# 612_jetracer_esp32s3_030004.net
KiCad netlist of a schematic drawn in EAGLE
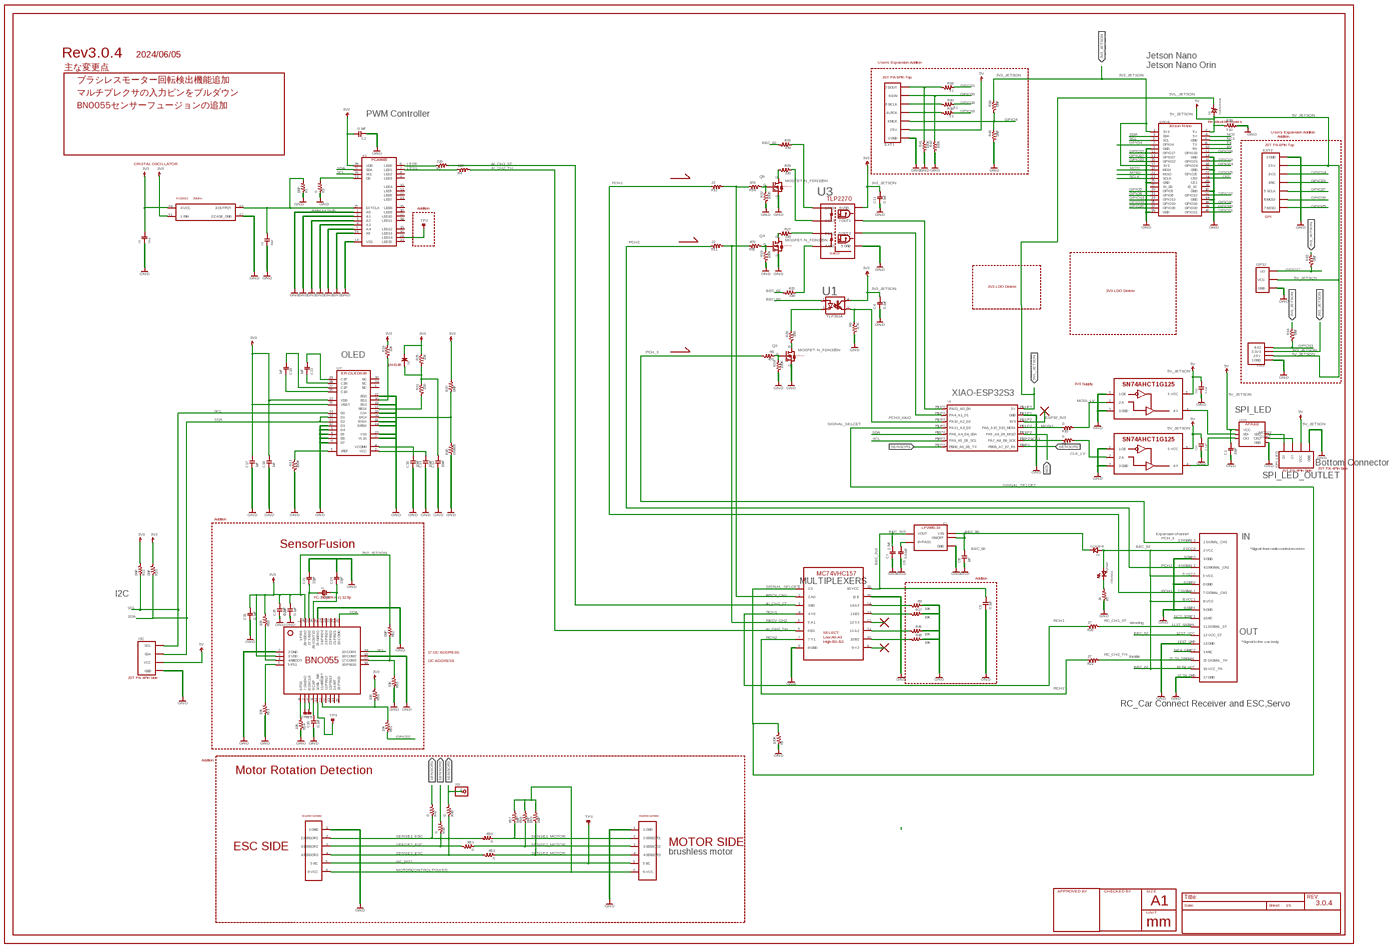
[diagram p0: schematic, sheet 1, overview]
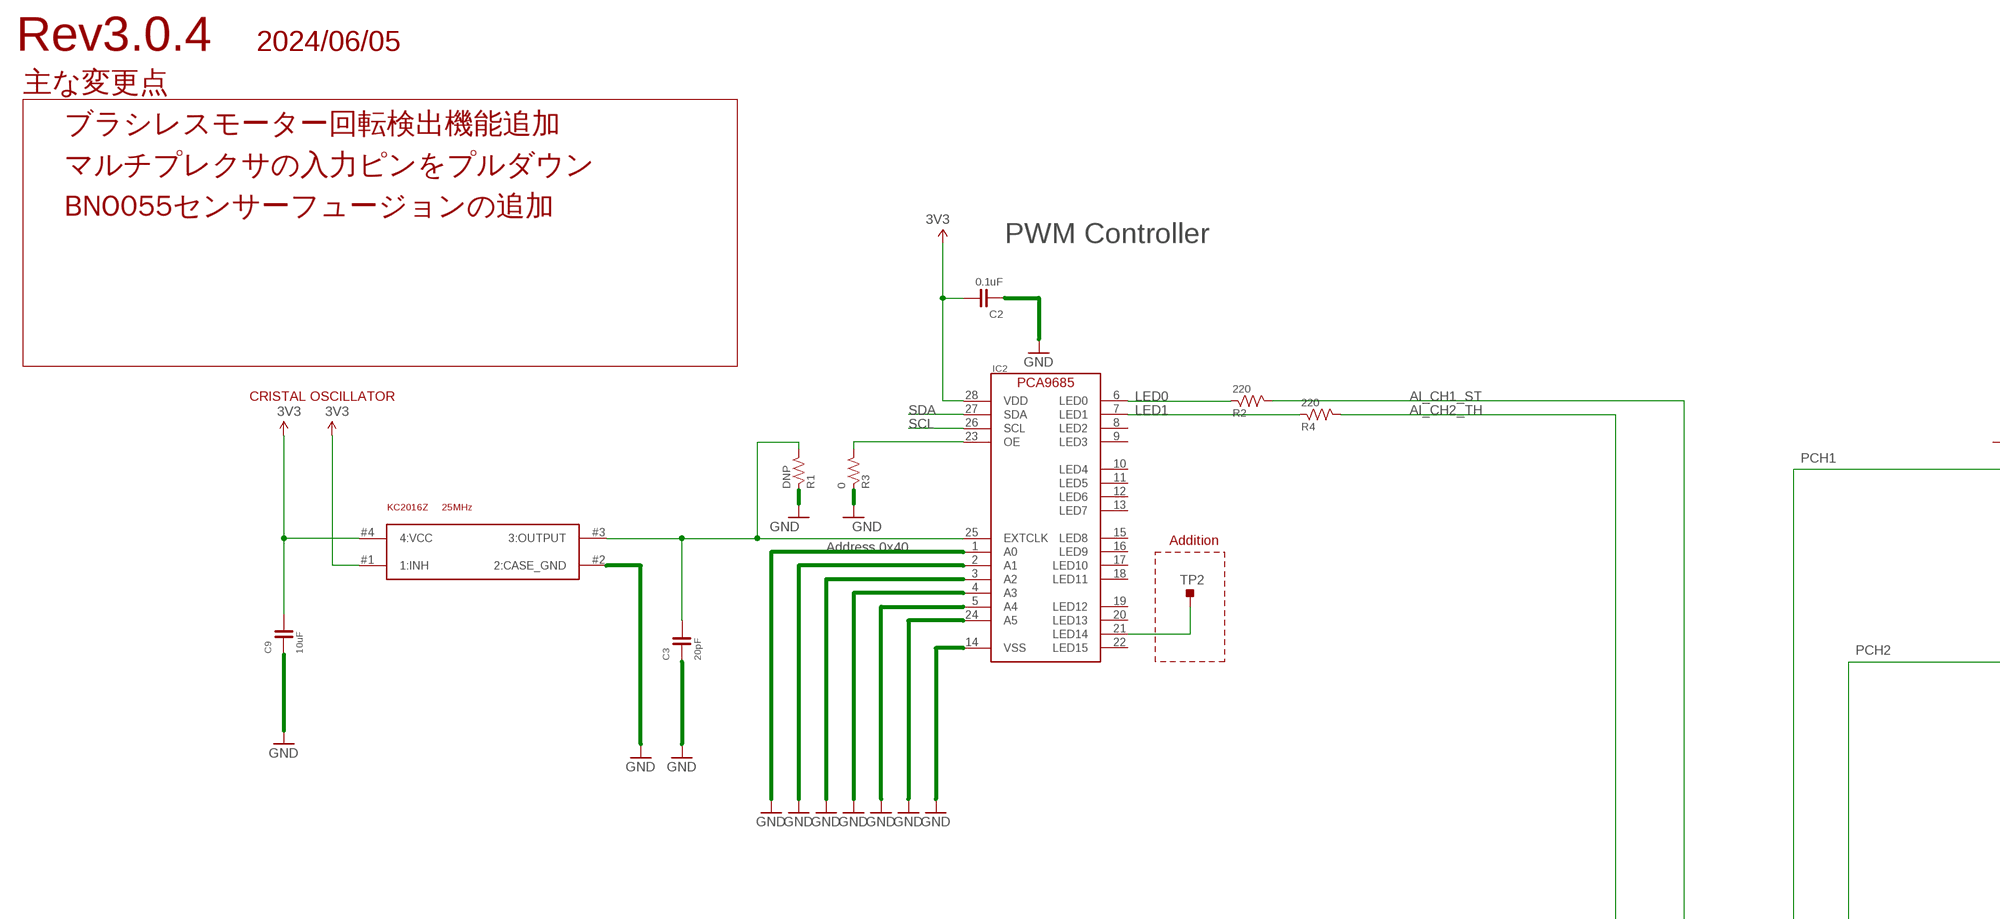
[diagram p1: schematic, sheet 1, part 1 of 4]
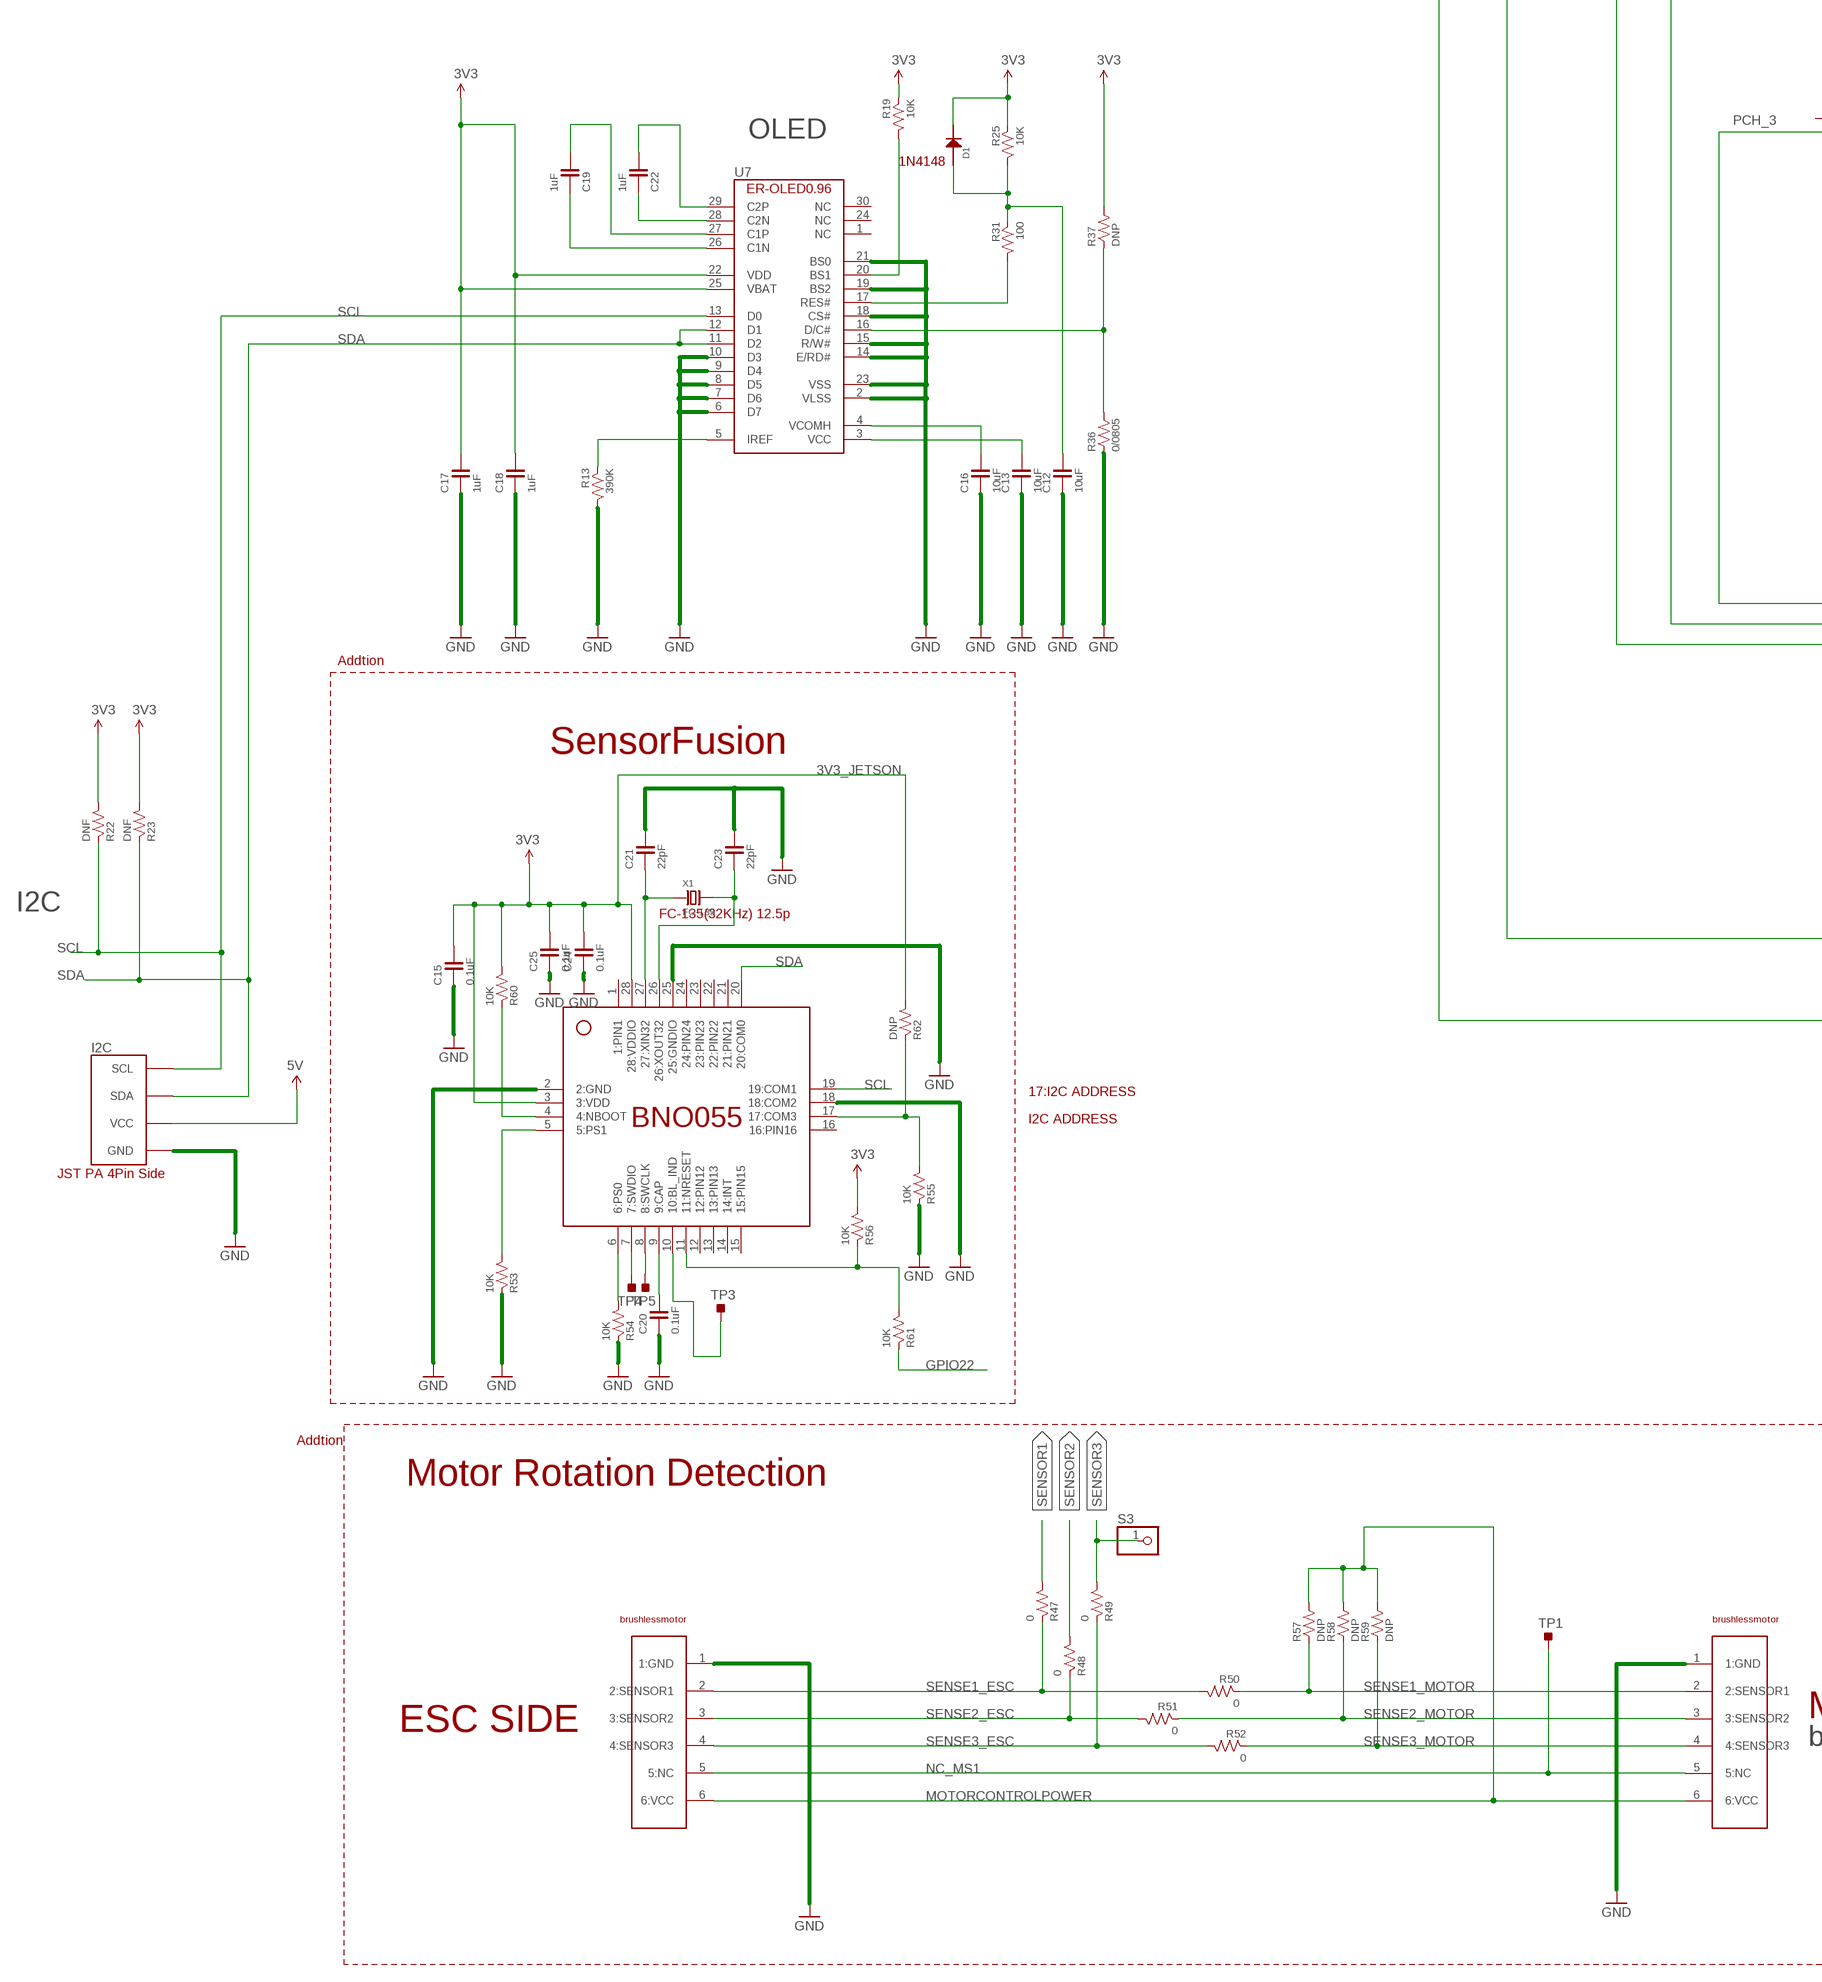
[diagram p2: schematic, sheet 1, part 2 of 4]
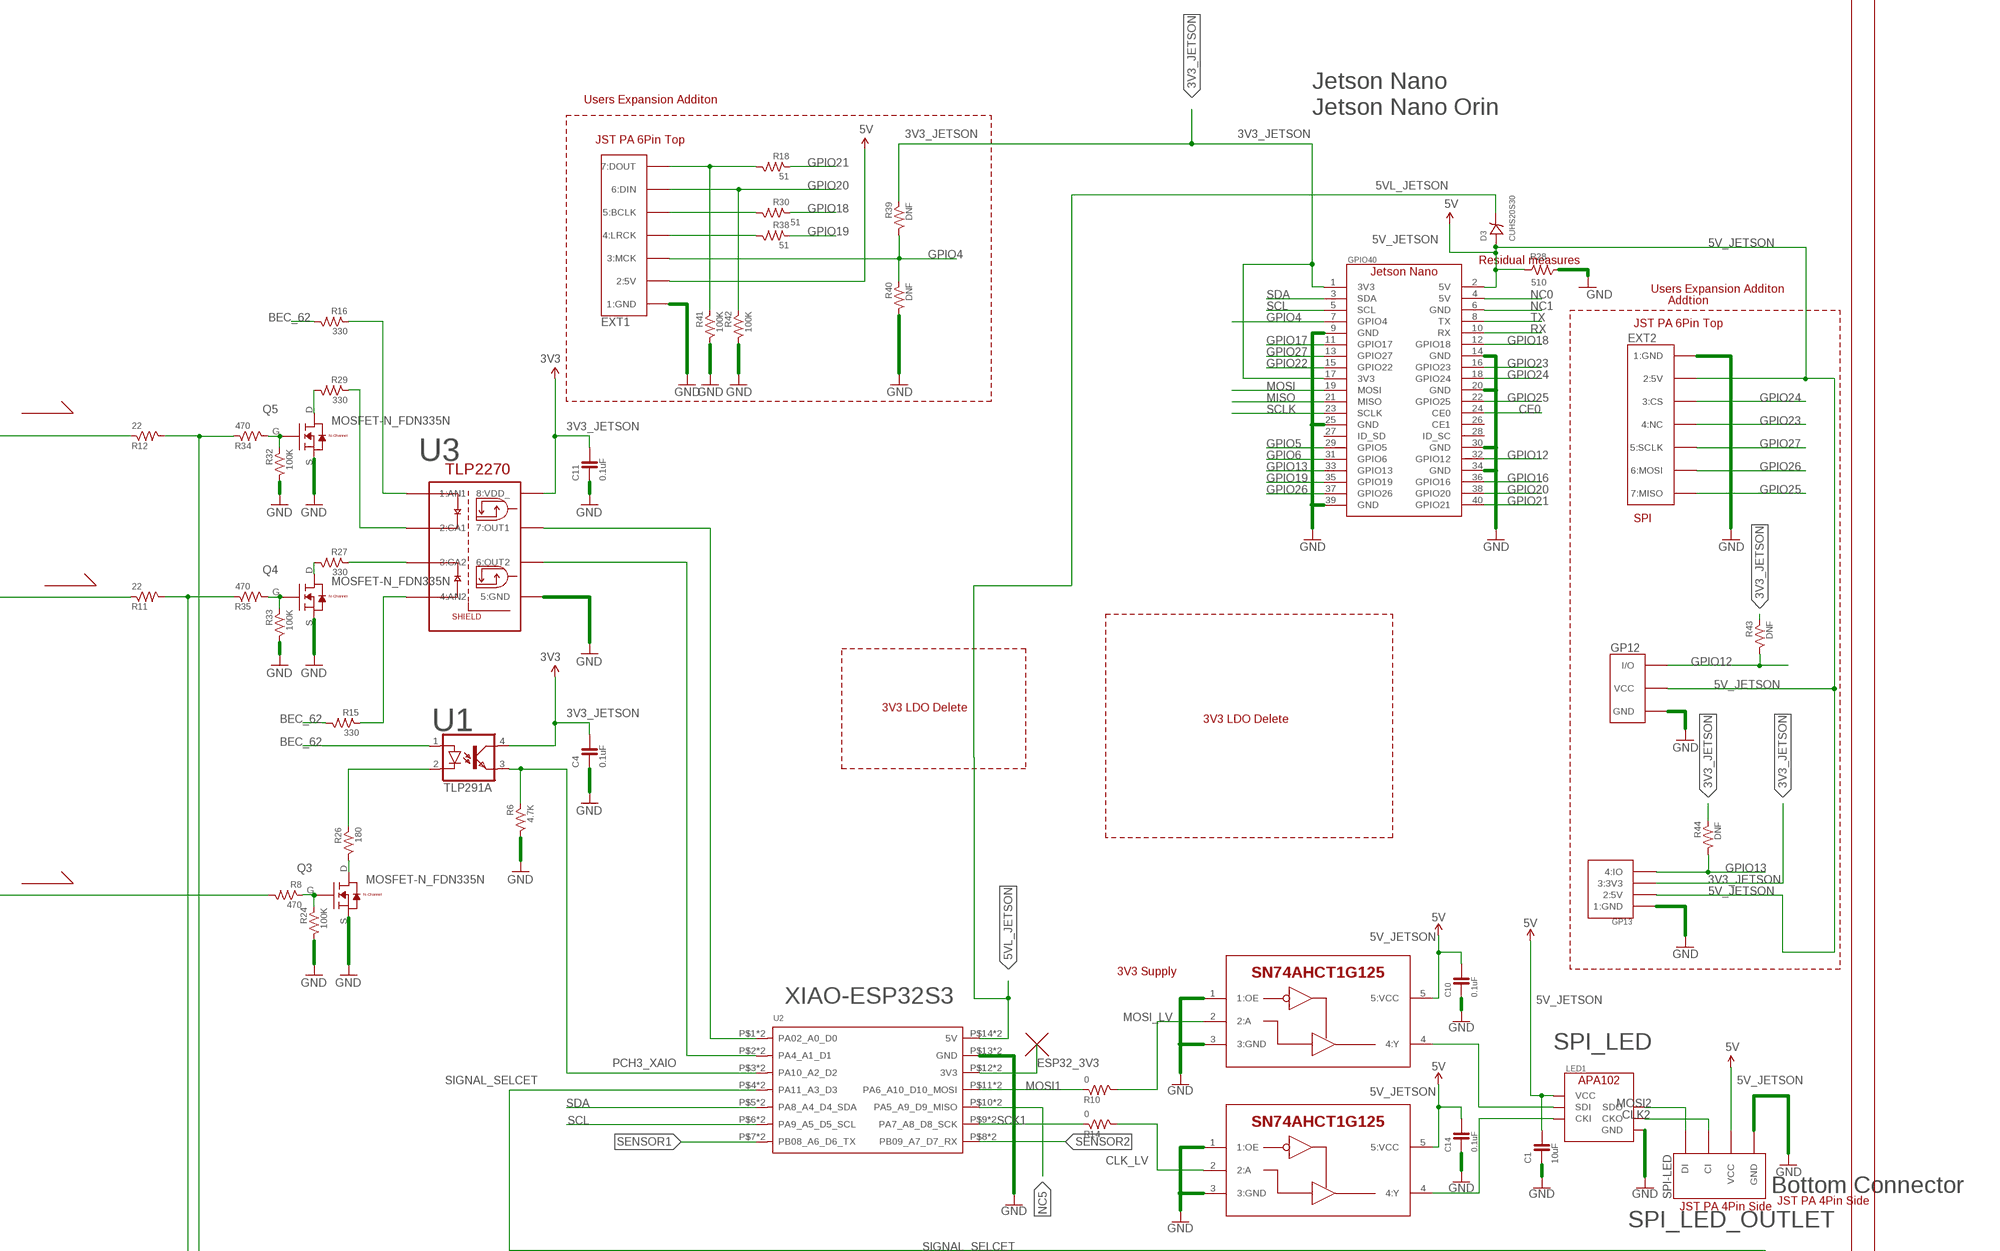
[diagram p3: schematic, sheet 1, part 3 of 4]
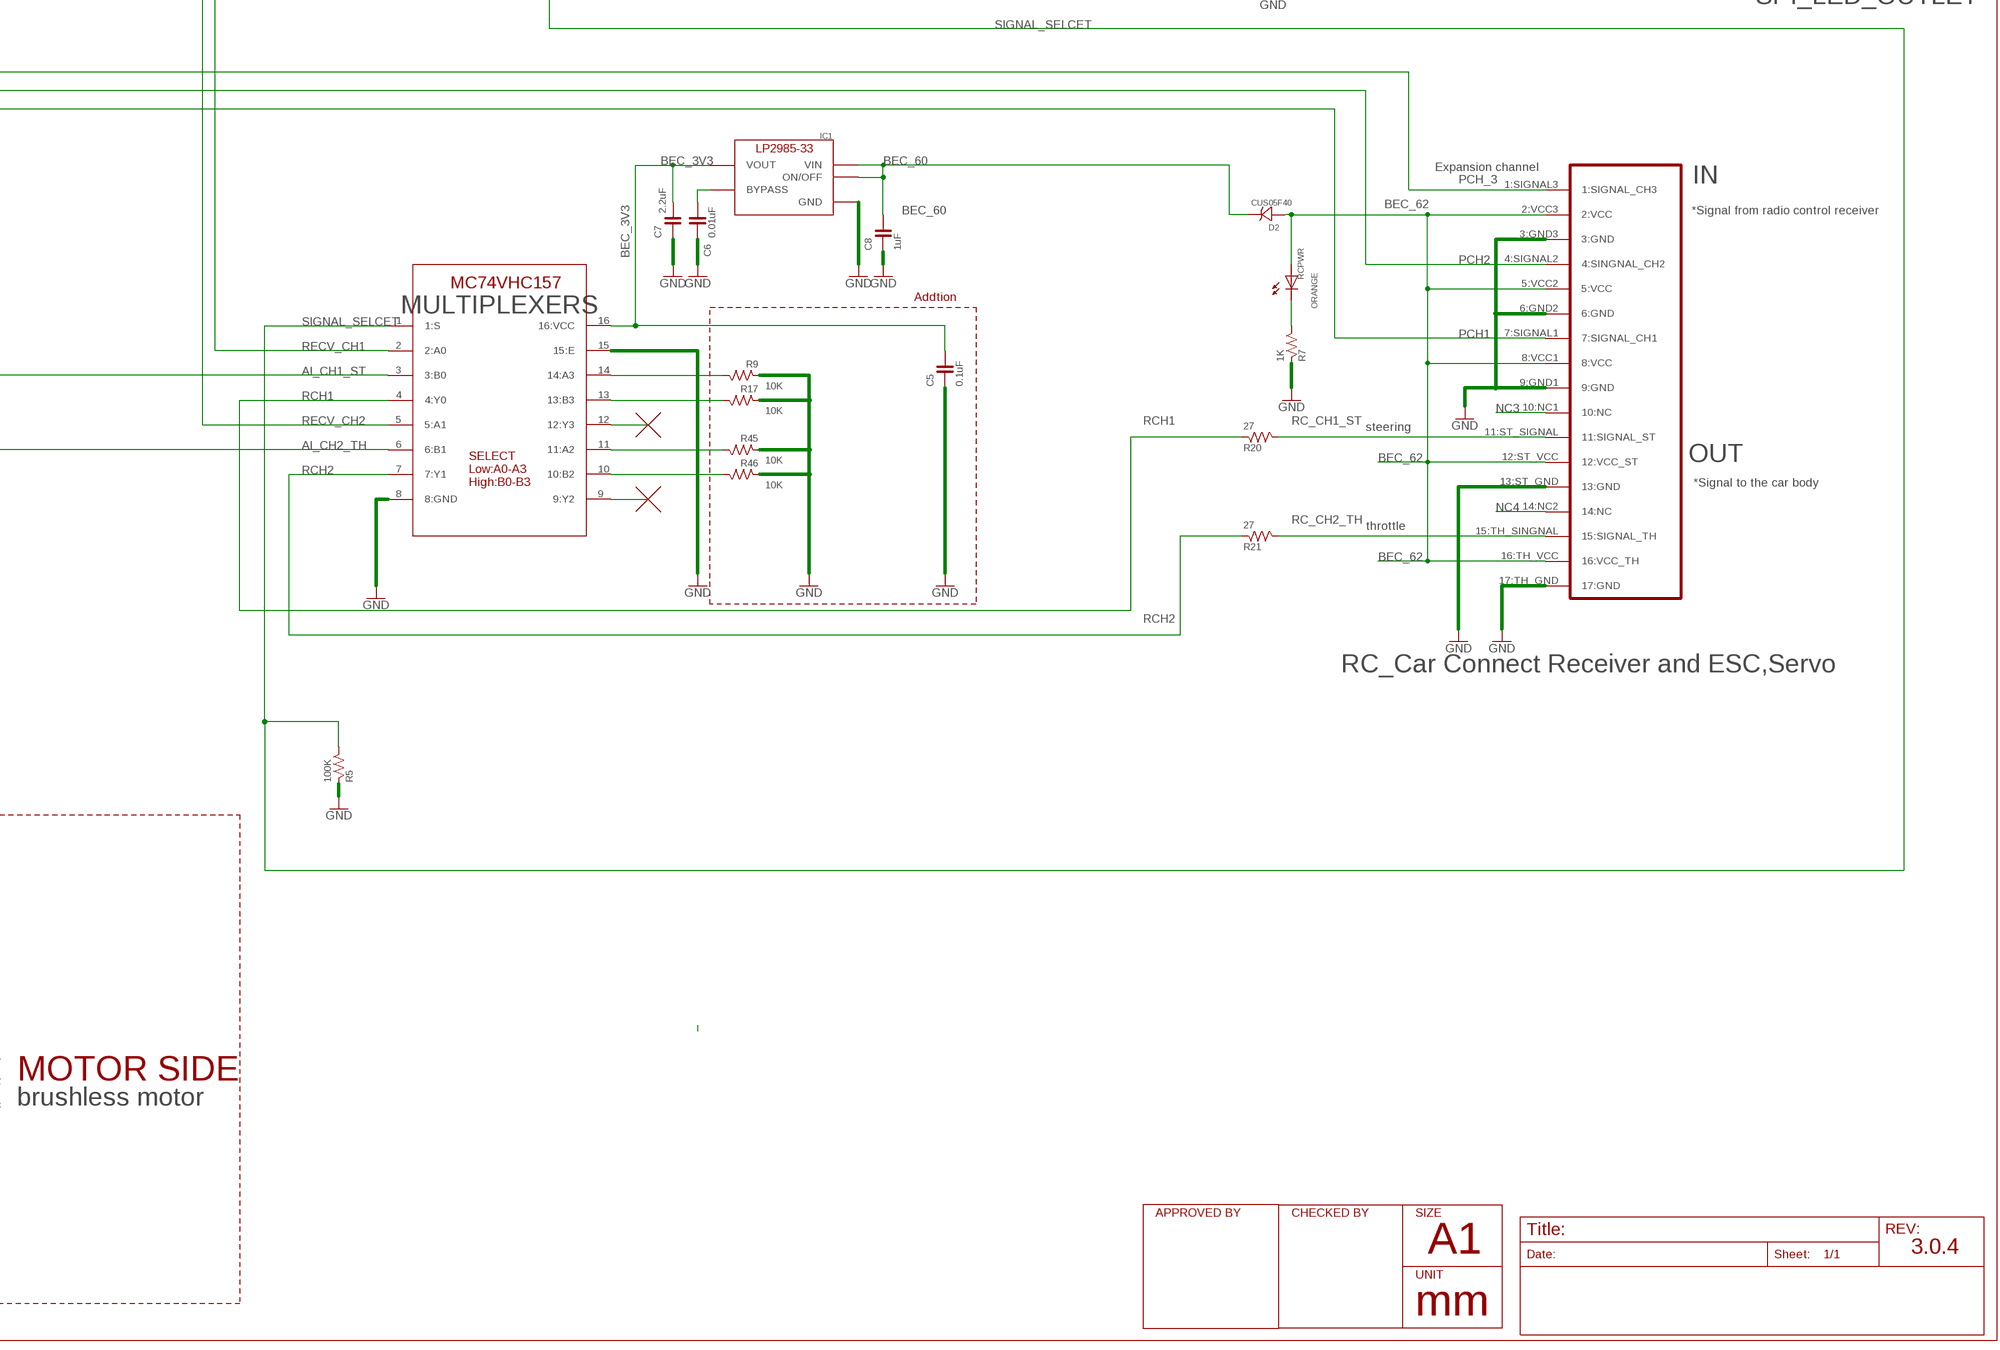
[diagram p4: schematic, sheet 1, part 4 of 4]

(export (version "E")
  (design (tool "Eeschema 10.0.6"))
  (components
    (comp (ref "C1")
      (value "10uF")
      (footprint "eagle-import:0603")
      (libsource (lib "eagle-import") (part "CAPACITOR-0603"))
    )
    (comp (ref "C2")
      (value "0.1uF")
      (footprint "eagle-import:0603")
      (libsource (lib "eagle-import") (part "CAPACITOR-0603"))
    )
    (comp (ref "C3")
      (value "20pF")
      (footprint "eagle-import:0402")
      (libsource (lib "eagle-import") (part "CAPACITOR-0402"))
    )
    (comp (ref "C4")
      (value "0.1uF")
      (footprint "eagle-import:0603")
      (libsource (lib "eagle-import") (part "CAPACITOR-0603"))
    )
    (comp (ref "C5")
      (value "0.1uF")
      (footprint "eagle-import:0603")
      (libsource (lib "eagle-import") (part "CAPACITOR-0603"))
    )
    (comp (ref "C6")
      (value "0.01uF")
      (footprint "eagle-import:0603")
      (libsource (lib "eagle-import") (part "CAPACITOR-0603"))
    )
    (comp (ref "C7")
      (value "2.2uF")
      (footprint "eagle-import:0603")
      (libsource (lib "eagle-import") (part "CAPACITOR-0603"))
    )
    (comp (ref "C8")
      (value "1uF")
      (footprint "eagle-import:0603")
      (libsource (lib "eagle-import") (part "CAPACITOR-0603"))
    )
    (comp (ref "C9")
      (value "10uF")
      (footprint "eagle-import:0402")
      (libsource (lib "eagle-import") (part "CAPACITOR-0402"))
    )
    (comp (ref "C10")
      (value "0.1uF")
      (footprint "eagle-import:0402")
      (libsource (lib "eagle-import") (part "CAPACITOR-0402"))
    )
    (comp (ref "C11")
      (value "0.1uF")
      (footprint "eagle-import:0603")
      (libsource (lib "eagle-import") (part "CAPACITOR-0603"))
    )
    (comp (ref "C12")
      (value "10uF")
      (footprint "eagle-import:0603")
      (libsource (lib "eagle-import") (part "CAPACITOR-0603"))
    )
    (comp (ref "C13")
      (value "10uF")
      (footprint "eagle-import:0603")
      (libsource (lib "eagle-import") (part "CAPACITOR-0603"))
    )
    (comp (ref "C14")
      (value "0.1uF")
      (footprint "eagle-import:0402")
      (libsource (lib "eagle-import") (part "CAPACITOR-0402"))
    )
    (comp (ref "C15")
      (value "0.1uF")
      (footprint "eagle-import:0402")
      (libsource (lib "eagle-import") (part "CAPACITOR-0402"))
    )
    (comp (ref "C16")
      (value "10uF")
      (footprint "eagle-import:0603")
      (libsource (lib "eagle-import") (part "CAPACITOR-0603"))
    )
    (comp (ref "C17")
      (value "1uF")
      (footprint "eagle-import:0603")
      (libsource (lib "eagle-import") (part "CAPACITOR-0603"))
    )
    (comp (ref "C18")
      (value "1uF")
      (footprint "eagle-import:0603")
      (libsource (lib "eagle-import") (part "CAPACITOR-0603"))
    )
    (comp (ref "C19")
      (value "1uF")
      (footprint "eagle-import:0603")
      (libsource (lib "eagle-import") (part "CAPACITOR-0603"))
    )
    (comp (ref "C20")
      (value "0.1uF")
      (footprint "eagle-import:0402")
      (libsource (lib "eagle-import") (part "CAPACITOR-0402"))
    )
    (comp (ref "C21")
      (value "22pF")
      (footprint "eagle-import:0402")
      (libsource (lib "eagle-import") (part "CAPACITOR-0402"))
    )
    (comp (ref "C22")
      (value "1uF")
      (footprint "eagle-import:0603")
      (libsource (lib "eagle-import") (part "CAPACITOR-0603"))
    )
    (comp (ref "C23")
      (value "22pF")
      (footprint "eagle-import:0402")
      (libsource (lib "eagle-import") (part "CAPACITOR-0402"))
    )
    (comp (ref "C24")
      (value "0.1uF")
      (footprint "eagle-import:0402")
      (libsource (lib "eagle-import") (part "CAPACITOR-0402"))
    )
    (comp (ref "C25")
      (value "0.1uF")
      (footprint "eagle-import:0402")
      (libsource (lib "eagle-import") (part "CAPACITOR-0402"))
    )
    (comp (ref "D1")
      (value "1N4148")
      (footprint "eagle-import:1N4148W")
      (libsource (lib "eagle-import") (part "1N4148"))
    )
    (comp (ref "D2")
      (value "CUS05F40")
      (footprint "eagle-import:CUS05F40")
      (libsource (lib "eagle-import") (part "CUS05F40"))
    )
    (comp (ref "D3")
      (value "CUHS20S30")
      (footprint "eagle-import:US2H")
      (libsource (lib "eagle-import") (part "CUHS20S30"))
    )
    (comp (ref "ESC_CON")
      (value "BRUSHLESSMOTOR_CON")
      (footprint "eagle-import:B6B-ZR")
      (libsource (lib "eagle-import") (part "BRUSHLESSMOTOR_CON"))
    )
    (comp (ref "EXT1")
      (value "FABO-I2S-7PIN")
      (footprint "eagle-import:SPI-B07B-PASK-1")
      (libsource (lib "eagle-import") (part "FABO-I2S-7PIN"))
    )
    (comp (ref "EXT2")
      (value "FABO-SPI-7PIN")
      (footprint "eagle-import:SPI-B07B-PASK-1")
      (libsource (lib "eagle-import") (part "FABO-SPI-7PIN"))
    )
    (comp (ref "GP12")
      (value "FABO_BRICK_3PIN-B03B-PASK-1")
      (footprint "eagle-import:FABO_BRICK_3PIN_B03B-PASK-1")
      (libsource (lib "eagle-import") (part "FABO_BRICK_3PIN-B03B-PASK-1"))
    )
    (comp (ref "GP13")
      (value "FABO-GPIO-2G")
      (footprint "eagle-import:GPIO-B04B-PASK-1")
      (libsource (lib "eagle-import") (part "FABO-GPIO-2G"))
    )
    (comp (ref "GPIO40")
      (value "JETSON_NANOJETSON_NANO_OVERALL")
      (footprint "eagle-import:JETSON_NANO_DEMENTION")
      (libsource (lib "eagle-import") (part "JETSON_NANOJETSON_NANO_OVERALL"))
    )
    (comp (ref "I2C")
      (value "FABO-I2C")
      (footprint "eagle-import:I2C-SM04B-PASS-1-FL")
      (libsource (lib "eagle-import") (part "FABO-I2C"))
    )
    (comp (ref "IC1")
      (value "LP2985-33DBVR")
      (footprint "eagle-import:SOT-23-5")
      (libsource (lib "eagle-import") (part "LP2985-33DBVR"))
    )
    (comp (ref "IC2")
      (value "PCA9685PW,BS")
      (footprint "eagle-import:PCA9685")
      (libsource (lib "eagle-import") (part "PCA9685PW,BS"))
    )
    (comp (ref "LED1")
      (value "APA102_IPIXEL")
      (footprint "eagle-import:APA102_2020")
      (libsource (lib "eagle-import") (part "APA102_IPIXEL"))
    )
    (comp (ref "MOTOR")
      (value "BRUSHLESSMOTOR_CON")
      (footprint "eagle-import:B6B-ZR")
      (libsource (lib "eagle-import") (part "BRUSHLESSMOTOR_CON"))
    )
    (comp (ref "Q3")
      (value "MOSFET-N_FDN335N")
      (footprint "eagle-import:SUPERSOT-3")
      (libsource (lib "eagle-import") (part "MOSFET-N_FDN335N"))
    )
    (comp (ref "Q4")
      (value "MOSFET-N_FDN335N")
      (footprint "eagle-import:SUPERSOT-3")
      (libsource (lib "eagle-import") (part "MOSFET-N_FDN335N"))
    )
    (comp (ref "Q5")
      (value "MOSFET-N_FDN335N")
      (footprint "eagle-import:SUPERSOT-3")
      (libsource (lib "eagle-import") (part "MOSFET-N_FDN335N"))
    )
    (comp (ref "R1")
      (value "DNP")
      (footprint "eagle-import:0603")
      (libsource (lib "eagle-import") (part "RESISTOR-0603"))
    )
    (comp (ref "R2")
      (value "220")
      (footprint "eagle-import:0603")
      (libsource (lib "eagle-import") (part "RESISTOR-0603"))
    )
    (comp (ref "R3")
      (value "0")
      (footprint "eagle-import:0603")
      (libsource (lib "eagle-import") (part "RESISTOR-0603"))
    )
    (comp (ref "R4")
      (value "220")
      (footprint "eagle-import:0603")
      (libsource (lib "eagle-import") (part "RESISTOR-0603"))
    )
    (comp (ref "R5")
      (value "100K")
      (footprint "eagle-import:0603")
      (libsource (lib "eagle-import") (part "RESISTOR-0603"))
    )
    (comp (ref "R6")
      (value "4.7K")
      (footprint "eagle-import:0603")
      (libsource (lib "eagle-import") (part "RESISTOR-0603"))
    )
    (comp (ref "R7")
      (value "1K")
      (footprint "eagle-import:0603")
      (libsource (lib "eagle-import") (part "RESISTOR-0603"))
    )
    (comp (ref "R8")
      (value "470")
      (footprint "eagle-import:0603")
      (libsource (lib "eagle-import") (part "RESISTOR-0603"))
    )
    (comp (ref "R9")
      (value "10K")
      (footprint "eagle-import:0603")
      (libsource (lib "eagle-import") (part "RESISTOR-0603"))
    )
    (comp (ref "R10")
      (value "0")
      (footprint "eagle-import:0603")
      (libsource (lib "eagle-import") (part "RESISTOR-0603"))
    )
    (comp (ref "R11")
      (value "22")
      (footprint "eagle-import:0603")
      (libsource (lib "eagle-import") (part "RESISTOR-0603"))
    )
    (comp (ref "R12")
      (value "22")
      (footprint "eagle-import:0603")
      (libsource (lib "eagle-import") (part "RESISTOR-0603"))
    )
    (comp (ref "R13")
      (value "390K")
      (footprint "eagle-import:0603")
      (libsource (lib "eagle-import") (part "RESISTOR-0603"))
    )
    (comp (ref "R14")
      (value "0")
      (footprint "eagle-import:0603")
      (libsource (lib "eagle-import") (part "RESISTOR-0603"))
    )
    (comp (ref "R15")
      (value "330")
      (footprint "eagle-import:0603")
      (libsource (lib "eagle-import") (part "RESISTOR-0603"))
    )
    (comp (ref "R16")
      (value "330")
      (footprint "eagle-import:0603")
      (libsource (lib "eagle-import") (part "RESISTOR-0603"))
    )
    (comp (ref "R17")
      (value "10K")
      (footprint "eagle-import:0603")
      (libsource (lib "eagle-import") (part "RESISTOR-0603"))
    )
    (comp (ref "R18")
      (value "51")
      (footprint "eagle-import:0603")
      (libsource (lib "eagle-import") (part "RESISTOR-0603"))
    )
    (comp (ref "R19")
      (value "10K")
      (footprint "eagle-import:0603")
      (libsource (lib "eagle-import") (part "RESISTOR-0603"))
    )
    (comp (ref "R20")
      (value "27")
      (footprint "eagle-import:0603")
      (libsource (lib "eagle-import") (part "RESISTOR-0603"))
    )
    (comp (ref "R21")
      (value "27")
      (footprint "eagle-import:0603")
      (libsource (lib "eagle-import") (part "RESISTOR-0603"))
    )
    (comp (ref "R22")
      (value "DNF")
      (footprint "eagle-import:0603")
      (libsource (lib "eagle-import") (part "RESISTOR-0603"))
    )
    (comp (ref "R23")
      (value "DNF")
      (footprint "eagle-import:0603")
      (libsource (lib "eagle-import") (part "RESISTOR-0603"))
    )
    (comp (ref "R24")
      (value "100K")
      (footprint "eagle-import:0603")
      (libsource (lib "eagle-import") (part "RESISTOR-0603"))
    )
    (comp (ref "R25")
      (value "10K")
      (footprint "eagle-import:0603")
      (libsource (lib "eagle-import") (part "RESISTOR-0603"))
    )
    (comp (ref "R26")
      (value "180")
      (footprint "eagle-import:0603")
      (libsource (lib "eagle-import") (part "RESISTOR-0603"))
    )
    (comp (ref "R27")
      (value "330")
      (footprint "eagle-import:0603")
      (libsource (lib "eagle-import") (part "RESISTOR-0603"))
    )
    (comp (ref "R28")
      (value "510")
      (footprint "eagle-import:0805")
      (libsource (lib "eagle-import") (part "RESISTOR-0805"))
    )
    (comp (ref "R29")
      (value "330")
      (footprint "eagle-import:0603")
      (libsource (lib "eagle-import") (part "RESISTOR-0603"))
    )
    (comp (ref "R30")
      (value "51")
      (footprint "eagle-import:0603")
      (libsource (lib "eagle-import") (part "RESISTOR-0603"))
    )
    (comp (ref "R31")
      (value "100")
      (footprint "eagle-import:0603")
      (libsource (lib "eagle-import") (part "RESISTOR-0603"))
    )
    (comp (ref "R32")
      (value "100K")
      (footprint "eagle-import:0603")
      (libsource (lib "eagle-import") (part "RESISTOR-0603"))
    )
    (comp (ref "R33")
      (value "100K")
      (footprint "eagle-import:0603")
      (libsource (lib "eagle-import") (part "RESISTOR-0603"))
    )
    (comp (ref "R34")
      (value "470")
      (footprint "eagle-import:0603")
      (libsource (lib "eagle-import") (part "RESISTOR-0603"))
    )
    (comp (ref "R35")
      (value "470")
      (footprint "eagle-import:0603")
      (libsource (lib "eagle-import") (part "RESISTOR-0603"))
    )
    (comp (ref "R36")
      (value "0/0805")
      (footprint "eagle-import:0805")
      (libsource (lib "eagle-import") (part "RESISTOR-0805"))
    )
    (comp (ref "R37")
      (value "DNP")
      (footprint "eagle-import:0805")
      (fields (field (name "SPICEPREFIX") "R"))
      (libsource (lib "eagle-import") (part "RESISTOR-0805"))
    )
    (comp (ref "R38")
      (value "51")
      (footprint "eagle-import:0603")
      (libsource (lib "eagle-import") (part "RESISTOR-0603"))
    )
    (comp (ref "R39")
      (value "DNF")
      (footprint "eagle-import:0603")
      (libsource (lib "eagle-import") (part "RESISTOR-0603"))
    )
    (comp (ref "R40")
      (value "DNF")
      (footprint "eagle-import:0603")
      (libsource (lib "eagle-import") (part "RESISTOR-0603"))
    )
    (comp (ref "R41")
      (value "100K")
      (footprint "eagle-import:0603")
      (libsource (lib "eagle-import") (part "RESISTOR-0603"))
    )
    (comp (ref "R42")
      (value "100K")
      (footprint "eagle-import:0603")
      (libsource (lib "eagle-import") (part "RESISTOR-0603"))
    )
    (comp (ref "R43")
      (value "DNF")
      (footprint "eagle-import:0603")
      (libsource (lib "eagle-import") (part "RESISTOR-0603"))
    )
    (comp (ref "R44")
      (value "DNF")
      (footprint "eagle-import:0603")
      (libsource (lib "eagle-import") (part "RESISTOR-0603"))
    )
    (comp (ref "R45")
      (value "10K")
      (footprint "eagle-import:0603")
      (libsource (lib "eagle-import") (part "RESISTOR-0603"))
    )
    (comp (ref "R46")
      (value "10K")
      (footprint "eagle-import:0603")
      (libsource (lib "eagle-import") (part "RESISTOR-0603"))
    )
    (comp (ref "R47")
      (value "0")
      (footprint "eagle-import:0603")
      (libsource (lib "eagle-import") (part "RESISTOR-0603"))
    )
    (comp (ref "R48")
      (value "0")
      (footprint "eagle-import:0603")
      (libsource (lib "eagle-import") (part "RESISTOR-0603"))
    )
    (comp (ref "R49")
      (value "0")
      (footprint "eagle-import:0603")
      (libsource (lib "eagle-import") (part "RESISTOR-0603"))
    )
    (comp (ref "R50")
      (value "0")
      (footprint "eagle-import:0603")
      (libsource (lib "eagle-import") (part "RESISTOR-0603"))
    )
    (comp (ref "R51")
      (value "0")
      (footprint "eagle-import:0603")
      (libsource (lib "eagle-import") (part "RESISTOR-0603"))
    )
    (comp (ref "R52")
      (value "0")
      (footprint "eagle-import:0603")
      (libsource (lib "eagle-import") (part "RESISTOR-0603"))
    )
    (comp (ref "R53")
      (value "10K")
      (footprint "eagle-import:0402")
      (libsource (lib "eagle-import") (part "RESISTOR-0402"))
    )
    (comp (ref "R54")
      (value "10K")
      (footprint "eagle-import:0402")
      (libsource (lib "eagle-import") (part "RESISTOR-0402"))
    )
    (comp (ref "R55")
      (value "10K")
      (footprint "eagle-import:0402")
      (libsource (lib "eagle-import") (part "RESISTOR-0402"))
    )
    (comp (ref "R56")
      (value "10K")
      (footprint "eagle-import:0402")
      (libsource (lib "eagle-import") (part "RESISTOR-0402"))
    )
    (comp (ref "R57")
      (value "DNP")
      (footprint "eagle-import:0402")
      (libsource (lib "eagle-import") (part "RESISTOR-0402"))
    )
    (comp (ref "R58")
      (value "DNP")
      (footprint "eagle-import:0402")
      (libsource (lib "eagle-import") (part "RESISTOR-0402"))
    )
    (comp (ref "R59")
      (value "DNP")
      (footprint "eagle-import:0402")
      (libsource (lib "eagle-import") (part "RESISTOR-0402"))
    )
    (comp (ref "R60")
      (value "10K")
      (footprint "eagle-import:0402")
      (libsource (lib "eagle-import") (part "RESISTOR-0402"))
    )
    (comp (ref "R61")
      (value "10K")
      (footprint "eagle-import:0402")
      (libsource (lib "eagle-import") (part "RESISTOR-0402"))
    )
    (comp (ref "R62")
      (value "DNP")
      (footprint "eagle-import:0402")
      (fields (field (name "SPICEPREFIX") "R"))
      (libsource (lib "eagle-import") (part "RESISTOR-0402"))
    )
    (comp (ref "RCPWR")
      (value "ORANGE")
      (footprint "eagle-import:0603")
      (libsource (lib "eagle-import") (part "LED-0603"))
    )
    (comp (ref "S3")
      (value "PINHD-1X1")
      (footprint "eagle-import:1X01")
      (libsource (lib "eagle-import") (part "PINHD-1X1"))
    )
    (comp (ref "SPI-LED")
      (value "FABO-SPI-LED")
      (footprint "eagle-import:SPI-SM04B-PASS-1-FL")
      (libsource (lib "eagle-import") (part "FABO-SPI-LED"))
    )
    (comp (ref "TP1")
      (value "TESTPOINT_TPS-SMD-10SN")
      (footprint "eagle-import:TESTPOINT_SMD-10SN")
      (libsource (lib "eagle-import") (part "TESTPOINT_TPS-SMD-10SN"))
    )
    (comp (ref "TP2")
      (value "TESTPOINT_TPS-SMD-10SN")
      (footprint "eagle-import:TESTPOINT_SMD-10SN")
      (libsource (lib "eagle-import") (part "TESTPOINT_TPS-SMD-10SN"))
    )
    (comp (ref "TP3")
      (value "TESTPOINT_TPS-SMD-10SN")
      (footprint "eagle-import:TESTPOINT_SMD-10SN")
      (libsource (lib "eagle-import") (part "TESTPOINT_TPS-SMD-10SN"))
    )
    (comp (ref "TP4")
      (value "TESTPOINT_TPS-SMD-10SN")
      (footprint "eagle-import:TESTPOINT_SMD-10SN")
      (libsource (lib "eagle-import") (part "TESTPOINT_TPS-SMD-10SN"))
    )
    (comp (ref "TP5")
      (value "TESTPOINT_TPS-SMD-10SN")
      (footprint "eagle-import:TESTPOINT_SMD-10SN")
      (libsource (lib "eagle-import") (part "TESTPOINT_TPS-SMD-10SN"))
    )
    (comp (ref "U$1")
      (value "RC_17PIN_OUTIN")
      (footprint "eagle-import:PNHEADER_2.54_SMT_17PIN_RC_TT01_02")
      (libsource (lib "eagle-import") (part "RC_17PIN_OUTIN"))
    )
    (comp (ref "U$3")
      (value "MC74VHC157")
      (footprint "eagle-import:MC74VHC157_TSSOP-16")
      (libsource (lib "eagle-import") (part "MC74VHC157"))
    )
    (comp (ref "U$9")
      (value "SN74AHCT1G125")
      (footprint "eagle-import:SOT-1DOT1")
      (libsource (lib "eagle-import") (part "SN74AHCT1G125"))
    )
    (comp (ref "U$10")
      (value "SN74AHCT1G125")
      (footprint "eagle-import:SOT-1DOT1")
      (libsource (lib "eagle-import") (part "SN74AHCT1G125"))
    )
    (comp (ref "U$11")
      (value "KC2016Z")
      (footprint "eagle-import:KC2016Z")
      (libsource (lib "eagle-import") (part "KC2016Z"))
    )
    (comp (ref "U$13")
      (value "BNO055")
      (footprint "eagle-import:LGA")
      (libsource (lib "eagle-import") (part "BNO055"))
    )
    (comp (ref "U1")
      (value "TLP291A")
      (footprint "eagle-import:11-3C1")
      (libsource (lib "eagle-import") (part "TLP291A"))
    )
    (comp (ref "U2")
      (value "MOUDLE-SEEEDUINO-XIAO-ESP32C3")
      (footprint "eagle-import:MOUDLE14P-DIP")
      (libsource (lib "eagle-import") (part "MOUDLE-SEEEDUINO-XIAO-ESP32C3"))
    )
    (comp (ref "U3")
      (value "TLP2270")
      (footprint "eagle-import:TLP2270")
      (libsource (lib "eagle-import") (part "TLP2270"))
    )
    (comp (ref "U7")
      (value "ER-OLED0.96-1ER-CON30HT-1")
      (footprint "eagle-import:ER-CON30HT-1")
      (libsource (lib "eagle-import") (part "ER-OLED0.96-1ER-CON30HT-1"))
    )
    (comp (ref "X1")
      (value "FC-135")
      (footprint "eagle-import:FC-135")
      (libsource (lib "eagle-import") (part "FC-135"))
    )
  )
  (nets
    (net (code "1") (name "/AI_CH1_ST") (class "Default")
      (node (ref "R2") (pin "2") (pinfunction "2_2") (pintype "bidirectional"))
      (node (ref "U$3") (pin "3") (pinfunction "3:B0_3") (pintype "bidirectional"))
    )
    (net (code "2") (name "/AI_CH2_TH") (class "Default")
      (node (ref "R4") (pin "2") (pinfunction "2_2") (pintype "bidirectional"))
      (node (ref "U$3") (pin "6") (pinfunction "6:B1_6") (pintype "bidirectional"))
    )
    (net (code "3") (name "/BEC_3V3") (class "Default")
      (node (ref "C5") (pin "2") (pinfunction "2_2") (pintype "passive"))
      (node (ref "C7") (pin "2") (pinfunction "2_2") (pintype "passive"))
      (node (ref "IC1") (pin "5") (pinfunction "VOUT_5") (pintype "output"))
      (node (ref "U$3") (pin "16") (pinfunction "16:VCC_16") (pintype "bidirectional"))
    )
    (net (code "4") (name "/BEC_60") (class "Default")
      (node (ref "C8") (pin "2") (pinfunction "2_2") (pintype "passive"))
      (node (ref "D2") (pin "C") (pinfunction "CATHODE_C") (pintype "bidirectional"))
      (node (ref "IC1") (pin "1") (pinfunction "VIN_1") (pintype "input"))
      (node (ref "IC1") (pin "3") (pinfunction "ON/OFF_3") (pintype "input"))
    )
    (net (code "5") (name "/BEC_62") (class "Default")
      (node (ref "D2") (pin "A") (pinfunction "ANODE_A") (pintype "bidirectional"))
      (node (ref "R15") (pin "2") (pinfunction "2_2") (pintype "bidirectional"))
      (node (ref "R16") (pin "2") (pinfunction "2_2") (pintype "bidirectional"))
      (node (ref "RCPWR") (pin "ANODE") (pinfunction "ANODE_ANODE") (pintype "passive"))
      (node (ref "U$1") (pin "12:ST_VCC") (pinfunction "12:VCC_ST_12:ST_VCC") (pintype "bidirectional"))
      (node (ref "U$1") (pin "16:TH_VCC") (pinfunction "16:VCC_TH_16:TH_VCC") (pintype "bidirectional"))
      (node (ref "U$1") (pin "2:VCC3") (pinfunction "2:VCC_2:VCC3") (pintype "bidirectional"))
      (node (ref "U$1") (pin "5:VCC2") (pinfunction "5:VCC_5:VCC2") (pintype "bidirectional"))
      (node (ref "U$1") (pin "8:VCC1") (pinfunction "8:VCC_8:VCC1") (pintype "bidirectional"))
      (node (ref "U1") (pin "1") (pinfunction "A_1") (pintype "passive"))
    )
    (net (code "6") (name "/CE0") (class "Default")
      (node (ref "GPIO40") (pin "24") (pinfunction "CE0_24") (pintype "bidirectional"))
    )
    (net (code "7") (name "/CLK2") (class "Default")
      (node (ref "LED1") (pin "CKO") (pinfunction "CKO_CKO") (pintype "bidirectional"))
      (node (ref "SPI-LED") (pin "CI") (pinfunction "CI_CI") (pintype "bidirectional"))
    )
    (net (code "8") (name "/CLK_LV") (class "Default")
      (node (ref "R14") (pin "2") (pinfunction "2_2") (pintype "bidirectional"))
      (node (ref "U$10") (pin "2") (pinfunction "2:A_2") (pintype "input"))
    )
    (net (code "9") (name "/ESP32_3V3") (class "Default")
      (node (ref "U2") (pin "P$12") (pinfunction "3V3_P$12") (pintype "bidirectional"))
      (node (ref "U2") (pin "P$26") (pinfunction "3V3_P$26") (pintype "bidirectional"))
    )
    (net (code "10") (name "/GPIO4") (class "Default")
      (node (ref "EXT1") (pin "3") (pinfunction "3:MCK_3") (pintype "bidirectional"))
      (node (ref "GPIO40") (pin "7") (pinfunction "GPIO4_7") (pintype "bidirectional"))
      (node (ref "R39") (pin "2") (pinfunction "2_2") (pintype "bidirectional"))
      (node (ref "R40") (pin "1") (pinfunction "1_1") (pintype "bidirectional"))
    )
    (net (code "11") (name "/GPIO5") (class "Default")
      (node (ref "GPIO40") (pin "29") (pinfunction "GPIO5_29") (pintype "bidirectional"))
    )
    (net (code "12") (name "/GPIO6") (class "Default")
      (node (ref "GPIO40") (pin "31") (pinfunction "GPIO6_31") (pintype "bidirectional"))
    )
    (net (code "13") (name "/GPIO12") (class "Default")
      (node (ref "GP12") (pin "I/O") (pinfunction "I/O_I/O") (pintype "bidirectional"))
      (node (ref "GPIO40") (pin "32") (pinfunction "GPIO12_32") (pintype "bidirectional"))
      (node (ref "R43") (pin "2") (pinfunction "2_2") (pintype "bidirectional"))
    )
    (net (code "14") (name "/GPIO13") (class "Default")
      (node (ref "GP13") (pin "IO") (pinfunction "4:IO_IO") (pintype "bidirectional"))
      (node (ref "GPIO40") (pin "33") (pinfunction "GPIO13_33") (pintype "bidirectional"))
      (node (ref "R44") (pin "2") (pinfunction "2_2") (pintype "bidirectional"))
    )
    (net (code "15") (name "/GPIO16") (class "Default")
      (node (ref "GPIO40") (pin "36") (pinfunction "GPIO16_36") (pintype "bidirectional"))
    )
    (net (code "16") (name "/GPIO17") (class "Default")
      (node (ref "GPIO40") (pin "11") (pinfunction "GPIO17_11") (pintype "bidirectional"))
    )
    (net (code "17") (name "/GPIO18") (class "Default")
      (node (ref "GPIO40") (pin "12") (pinfunction "GPIO18_12") (pintype "bidirectional"))
      (node (ref "R30") (pin "1") (pinfunction "1_1") (pintype "bidirectional"))
    )
    (net (code "18") (name "/GPIO19") (class "Default")
      (node (ref "GPIO40") (pin "35") (pinfunction "GPIO19_35") (pintype "bidirectional"))
      (node (ref "R38") (pin "1") (pinfunction "1_1") (pintype "bidirectional"))
    )
    (net (code "19") (name "/GPIO20") (class "Default")
      (node (ref "EXT1") (pin "6") (pinfunction "6:DIN_6") (pintype "bidirectional"))
      (node (ref "GPIO40") (pin "38") (pinfunction "GPIO20_38") (pintype "bidirectional"))
      (node (ref "R42") (pin "1") (pinfunction "1_1") (pintype "bidirectional"))
    )
    (net (code "20") (name "/GPIO21") (class "Default")
      (node (ref "GPIO40") (pin "40") (pinfunction "GPIO21_40") (pintype "bidirectional"))
      (node (ref "R18") (pin "1") (pinfunction "1_1") (pintype "bidirectional"))
    )
    (net (code "21") (name "/GPIO22") (class "Default")
      (node (ref "GPIO40") (pin "15") (pinfunction "GPIO22_15") (pintype "bidirectional"))
      (node (ref "R61") (pin "1") (pinfunction "1_1") (pintype "bidirectional"))
    )
    (net (code "22") (name "/GPIO23") (class "Default")
      (node (ref "EXT2") (pin "4") (pinfunction "4:NC_4") (pintype "bidirectional"))
      (node (ref "GPIO40") (pin "16") (pinfunction "GPIO23_16") (pintype "bidirectional"))
    )
    (net (code "23") (name "/GPIO24") (class "Default")
      (node (ref "EXT2") (pin "3") (pinfunction "3:CS_3") (pintype "bidirectional"))
      (node (ref "GPIO40") (pin "18") (pinfunction "GPIO24_18") (pintype "bidirectional"))
    )
    (net (code "24") (name "/GPIO25") (class "Default")
      (node (ref "EXT2") (pin "7") (pinfunction "7:MISO_7") (pintype "bidirectional"))
      (node (ref "GPIO40") (pin "22") (pinfunction "GPIO25_22") (pintype "bidirectional"))
    )
    (net (code "25") (name "/GPIO26") (class "Default")
      (node (ref "EXT2") (pin "6") (pinfunction "6:MOSI_6") (pintype "bidirectional"))
      (node (ref "GPIO40") (pin "37") (pinfunction "GPIO26_37") (pintype "bidirectional"))
    )
    (net (code "26") (name "/GPIO27") (class "Default")
      (node (ref "EXT2") (pin "5") (pinfunction "5:SCLK_5") (pintype "bidirectional"))
      (node (ref "GPIO40") (pin "13") (pinfunction "GPIO27_13") (pintype "bidirectional"))
    )
    (net (code "27") (name "/LED0") (class "Default")
      (node (ref "IC2") (pin "6") (pinfunction "LED0_6") (pintype "bidirectional"))
      (node (ref "R2") (pin "1") (pinfunction "1_1") (pintype "bidirectional"))
    )
    (net (code "28") (name "/LED1") (class "Default")
      (node (ref "IC2") (pin "7") (pinfunction "LED1_7") (pintype "bidirectional"))
      (node (ref "R4") (pin "1") (pinfunction "1_1") (pintype "bidirectional"))
    )
    (net (code "29") (name "/MISO") (class "Default")
      (node (ref "GPIO40") (pin "21") (pinfunction "MISO_21") (pintype "bidirectional"))
    )
    (net (code "30") (name "/MOSI") (class "Default")
      (node (ref "GPIO40") (pin "19") (pinfunction "MOSI_19") (pintype "bidirectional"))
    )
    (net (code "31") (name "/MOSI1") (class "Default")
      (node (ref "R10") (pin "1") (pinfunction "1_1") (pintype "bidirectional"))
      (node (ref "U2") (pin "P$11") (pinfunction "PA6_A10_D10_MOSI_P$11") (pintype "bidirectional"))
      (node (ref "U2") (pin "P$25") (pinfunction "PA6_A10_D10_MOSI_P$25") (pintype "bidirectional"))
    )
    (net (code "32") (name "/MOSI2") (class "Default")
      (node (ref "LED1") (pin "SDO") (pinfunction "SDO_SDO") (pintype "bidirectional"))
      (node (ref "SPI-LED") (pin "DI") (pinfunction "DI_DI") (pintype "bidirectional"))
    )
    (net (code "33") (name "/MOSI_LV") (class "Default")
      (node (ref "R10") (pin "2") (pinfunction "2_2") (pintype "bidirectional"))
      (node (ref "U$9") (pin "2") (pinfunction "2:A_2") (pintype "input"))
    )
    (net (code "34") (name "/MOTORCONTROLPOWER") (class "Default")
      (node (ref "ESC_CON") (pin "6") (pinfunction "6:VCC_6") (pintype "bidirectional"))
      (node (ref "MOTOR") (pin "6") (pinfunction "6:VCC_6") (pintype "bidirectional"))
      (node (ref "R57") (pin "2") (pinfunction "2_2") (pintype "bidirectional"))
      (node (ref "R58") (pin "2") (pinfunction "2_2") (pintype "bidirectional"))
      (node (ref "R59") (pin "2") (pinfunction "2_2") (pintype "bidirectional"))
    )
    (net (code "35") (name "/NC0") (class "Default")
      (node (ref "GPIO40") (pin "4") (pinfunction "5V_4") (pintype "bidirectional"))
    )
    (net (code "36") (name "/NC1") (class "Default")
      (node (ref "GPIO40") (pin "6") (pinfunction "GND_6") (pintype "bidirectional"))
    )
    (net (code "37") (name "/NC3") (class "Default")
      (node (ref "U$1") (pin "10:NC1") (pinfunction "10:NC_10:NC1") (pintype "bidirectional"))
    )
    (net (code "38") (name "/NC4") (class "Default")
      (node (ref "U$1") (pin "14:NC2") (pinfunction "14:NC_14:NC2") (pintype "bidirectional"))
    )
    (net (code "39") (name "/NC_MS1") (class "Default")
      (node (ref "ESC_CON") (pin "5") (pinfunction "5:NC_5") (pintype "bidirectional"))
      (node (ref "MOTOR") (pin "5") (pinfunction "5:NC_5") (pintype "bidirectional"))
      (node (ref "TP1") (pin "TP") (pinfunction "TP_TP") (pintype "passive"))
    )
    (net (code "40") (name "/PCH1") (class "Default")
      (node (ref "R12") (pin "1") (pinfunction "1_1") (pintype "bidirectional"))
      (node (ref "U$1") (pin "7:SIGNAL1") (pinfunction "7:SIGNAL_CH1_7:SIGNAL1") (pintype "bidirectional"))
    )
    (net (code "41") (name "/PCH2") (class "Default")
      (node (ref "R11") (pin "1") (pinfunction "1_1") (pintype "bidirectional"))
      (node (ref "U$1") (pin "4:SIGNAL2") (pinfunction "4:SINGNAL_CH2_4:SIGNAL2") (pintype "bidirectional"))
    )
    (net (code "42") (name "/PCH3_XAIO") (class "Default")
      (node (ref "R6") (pin "1") (pinfunction "1_1") (pintype "bidirectional"))
      (node (ref "U1") (pin "3") (pinfunction "EMI_3") (pintype "passive"))
      (node (ref "U2") (pin "P$17") (pinfunction "PA10_A2_D2_P$17") (pintype "bidirectional"))
      (node (ref "U2") (pin "P$3") (pinfunction "PA10_A2_D2_P$3") (pintype "bidirectional"))
    )
    (net (code "43") (name "/PCH_3") (class "Default")
      (node (ref "R8") (pin "2") (pinfunction "2_2") (pintype "bidirectional"))
      (node (ref "U$1") (pin "1:SIGNAL3") (pinfunction "1:SIGNAL_CH3_1:SIGNAL3") (pintype "bidirectional"))
    )
    (net (code "44") (name "/RCH1") (class "Default")
      (node (ref "R20") (pin "1") (pinfunction "1_1") (pintype "bidirectional"))
      (node (ref "U$3") (pin "4") (pinfunction "4:Y0_4") (pintype "bidirectional"))
    )
    (net (code "45") (name "/RCH2") (class "Default")
      (node (ref "R21") (pin "1") (pinfunction "1_1") (pintype "bidirectional"))
      (node (ref "U$3") (pin "7") (pinfunction "7:Y1_7") (pintype "bidirectional"))
    )
    (net (code "46") (name "/RC_CH1_ST") (class "Default")
      (node (ref "R20") (pin "2") (pinfunction "2_2") (pintype "bidirectional"))
      (node (ref "U$1") (pin "11:ST_SIGNAL") (pinfunction "11:SIGNAL_ST_11:ST_SIGNAL") (pintype "bidirectional"))
    )
    (net (code "47") (name "/RC_CH2_TH") (class "Default")
      (node (ref "R21") (pin "2") (pinfunction "2_2") (pintype "bidirectional"))
      (node (ref "U$1") (pin "15:TH_SINGNAL") (pinfunction "15:SIGNAL_TH_15:TH_SINGNAL") (pintype "bidirectional"))
    )
    (net (code "48") (name "/RECV_CH1") (class "Default")
      (node (ref "R12") (pin "2") (pinfunction "2_2") (pintype "bidirectional"))
      (node (ref "R34") (pin "1") (pinfunction "1_1") (pintype "bidirectional"))
      (node (ref "U$3") (pin "2") (pinfunction "2:A0_2") (pintype "bidirectional"))
    )
    (net (code "49") (name "/RECV_CH2") (class "Default")
      (node (ref "R11") (pin "2") (pinfunction "2_2") (pintype "bidirectional"))
      (node (ref "R35") (pin "1") (pinfunction "1_1") (pintype "bidirectional"))
      (node (ref "U$3") (pin "5") (pinfunction "5:A1_5") (pintype "bidirectional"))
    )
    (net (code "50") (name "/RX") (class "Default")
      (node (ref "GPIO40") (pin "10") (pinfunction "RX_10") (pintype "bidirectional"))
    )
    (net (code "51") (name "/SCK1") (class "Default")
      (node (ref "R14") (pin "1") (pinfunction "1_1") (pintype "bidirectional"))
      (node (ref "U2") (pin "P$23") (pinfunction "PA7_A8_D8_SCK_P$23") (pintype "bidirectional"))
      (node (ref "U2") (pin "P$9") (pinfunction "PA7_A8_D8_SCK_P$9") (pintype "bidirectional"))
    )
    (net (code "52") (name "/SCL") (class "Default")
      (node (ref "GPIO40") (pin "5") (pinfunction "SCL_5") (pintype "bidirectional"))
      (node (ref "I2C") (pin "SCL") (pinfunction "SCL_SCL") (pintype "bidirectional"))
      (node (ref "IC2") (pin "26") (pinfunction "SCL_26") (pintype "bidirectional"))
      (node (ref "R22") (pin "1") (pinfunction "1_1") (pintype "bidirectional"))
      (node (ref "U$13") (pin "19") (pinfunction "19:COM1_19") (pintype "bidirectional"))
      (node (ref "U2") (pin "P$20") (pinfunction "PA9_A5_D5_SCL_P$20") (pintype "bidirectional"))
      (node (ref "U2") (pin "P$6") (pinfunction "PA9_A5_D5_SCL_P$6") (pintype "bidirectional"))
      (node (ref "U7") (pin "13") (pinfunction "D0_13") (pintype "bidirectional"))
    )
    (net (code "53") (name "/SCLK") (class "Default")
      (node (ref "GPIO40") (pin "23") (pinfunction "SCLK_23") (pintype "bidirectional"))
    )
    (net (code "54") (name "/SDA") (class "Default")
      (node (ref "GPIO40") (pin "3") (pinfunction "SDA_3") (pintype "bidirectional"))
      (node (ref "I2C") (pin "SDA") (pinfunction "SDA_SDA") (pintype "bidirectional"))
      (node (ref "IC2") (pin "27") (pinfunction "SDA_27") (pintype "bidirectional"))
      (node (ref "R23") (pin "1") (pinfunction "1_1") (pintype "bidirectional"))
      (node (ref "U$13") (pin "20") (pinfunction "20:COM0_20") (pintype "bidirectional"))
      (node (ref "U2") (pin "P$19") (pinfunction "PA8_A4_D4_SDA_P$19") (pintype "bidirectional"))
      (node (ref "U2") (pin "P$5") (pinfunction "PA8_A4_D4_SDA_P$5") (pintype "bidirectional"))
      (node (ref "U7") (pin "11") (pinfunction "D2_11") (pintype "bidirectional"))
      (node (ref "U7") (pin "12") (pinfunction "D1_12") (pintype "bidirectional"))
    )
    (net (code "55") (name "/SENSE1_ESC") (class "Default")
      (node (ref "ESC_CON") (pin "2") (pinfunction "2:SENSOR1_2") (pintype "bidirectional"))
      (node (ref "R47") (pin "1") (pinfunction "1_1") (pintype "bidirectional"))
      (node (ref "R50") (pin "2") (pinfunction "2_2") (pintype "bidirectional"))
    )
    (net (code "56") (name "/SENSE1_MOTOR") (class "Default")
      (node (ref "MOTOR") (pin "2") (pinfunction "2:SENSOR1_2") (pintype "bidirectional"))
      (node (ref "R50") (pin "1") (pinfunction "1_1") (pintype "bidirectional"))
      (node (ref "R57") (pin "1") (pinfunction "1_1") (pintype "bidirectional"))
    )
    (net (code "57") (name "/SENSE2_ESC") (class "Default")
      (node (ref "ESC_CON") (pin "3") (pinfunction "3:SENSOR2_3") (pintype "bidirectional"))
      (node (ref "R48") (pin "1") (pinfunction "1_1") (pintype "bidirectional"))
      (node (ref "R51") (pin "2") (pinfunction "2_2") (pintype "bidirectional"))
    )
    (net (code "58") (name "/SENSE2_MOTOR") (class "Default")
      (node (ref "MOTOR") (pin "3") (pinfunction "3:SENSOR2_3") (pintype "bidirectional"))
      (node (ref "R51") (pin "1") (pinfunction "1_1") (pintype "bidirectional"))
      (node (ref "R58") (pin "1") (pinfunction "1_1") (pintype "bidirectional"))
    )
    (net (code "59") (name "/SENSE3_ESC") (class "Default")
      (node (ref "ESC_CON") (pin "4") (pinfunction "4:SENSOR3_4") (pintype "bidirectional"))
      (node (ref "R49") (pin "1") (pinfunction "1_1") (pintype "bidirectional"))
      (node (ref "R52") (pin "2") (pinfunction "2_2") (pintype "bidirectional"))
    )
    (net (code "60") (name "/SENSE3_MOTOR") (class "Default")
      (node (ref "MOTOR") (pin "4") (pinfunction "4:SENSOR3_4") (pintype "bidirectional"))
      (node (ref "R52") (pin "1") (pinfunction "1_1") (pintype "bidirectional"))
      (node (ref "R59") (pin "1") (pinfunction "1_1") (pintype "bidirectional"))
    )
    (net (code "61") (name "/SIGNAL_SELCET") (class "Default")
      (node (ref "R5") (pin "2") (pinfunction "2_2") (pintype "bidirectional"))
      (node (ref "U$3") (pin "1") (pinfunction "1:S_1") (pintype "bidirectional"))
      (node (ref "U2") (pin "P$18") (pinfunction "PA11_A3_D3_P$18") (pintype "bidirectional"))
      (node (ref "U2") (pin "P$4") (pinfunction "PA11_A3_D3_P$4") (pintype "bidirectional"))
    )
    (net (code "62") (name "/TX") (class "Default")
      (node (ref "GPIO40") (pin "8") (pinfunction "TX_8") (pintype "bidirectional"))
    )
    (net (code "63") (name "3V3_JETSON") (class "Default")
      (node (ref "C11") (pin "2") (pinfunction "2_2") (pintype "passive"))
      (node (ref "C15") (pin "2") (pinfunction "2_2") (pintype "passive"))
      (node (ref "C17") (pin "2") (pinfunction "2_2") (pintype "passive"))
      (node (ref "C18") (pin "2") (pinfunction "2_2") (pintype "passive"))
      (node (ref "C2") (pin "2") (pinfunction "2_2") (pintype "passive"))
      (node (ref "C24") (pin "2") (pinfunction "2_2") (pintype "passive"))
      (node (ref "C25") (pin "2") (pinfunction "2_2") (pintype "passive"))
      (node (ref "C4") (pin "2") (pinfunction "2_2") (pintype "passive"))
      (node (ref "C9") (pin "2") (pinfunction "2_2") (pintype "passive"))
      (node (ref "D1") (pin "CATHODE") (pinfunction "CATHODE_CATHODE") (pintype "bidirectional"))
      (node (ref "GP13") (pin "3V3") (pinfunction "3:3V3_3V3") (pintype "bidirectional"))
      (node (ref "GPIO40") (pin "1") (pinfunction "3V3_1") (pintype "bidirectional"))
      (node (ref "GPIO40") (pin "17") (pinfunction "3V3_17") (pintype "bidirectional"))
      (node (ref "IC2") (pin "28") (pinfunction "VDD_28") (pintype "bidirectional"))
      (node (ref "R19") (pin "1") (pinfunction "1_1") (pintype "bidirectional"))
      (node (ref "R22") (pin "2") (pinfunction "2_2") (pintype "bidirectional"))
      (node (ref "R23") (pin "2") (pinfunction "2_2") (pintype "bidirectional"))
      (node (ref "R25") (pin "1") (pinfunction "1_1") (pintype "bidirectional"))
      (node (ref "R37") (pin "2") (pinfunction "2_2") (pintype "bidirectional"))
      (node (ref "R39") (pin "1") (pinfunction "1_1") (pintype "bidirectional"))
      (node (ref "R43") (pin "1") (pinfunction "1_1") (pintype "bidirectional"))
      (node (ref "R44") (pin "1") (pinfunction "1_1") (pintype "bidirectional"))
      (node (ref "R56") (pin "2") (pinfunction "2_2") (pintype "bidirectional"))
      (node (ref "R60") (pin "2") (pinfunction "2_2") (pintype "bidirectional"))
      (node (ref "R62") (pin "2") (pinfunction "2_2") (pintype "bidirectional"))
      (node (ref "U$11") (pin "#1") (pinfunction "1:INH_#1") (pintype "bidirectional"))
      (node (ref "U$11") (pin "#4") (pinfunction "4:VCC_#4") (pintype "bidirectional"))
      (node (ref "U$13") (pin "28") (pinfunction "28:VDDIO_28") (pintype "power_in"))
      (node (ref "U$13") (pin "3") (pinfunction "3:VDD_3") (pintype "power_in"))
      (node (ref "U1") (pin "4") (pinfunction "COL_4") (pintype "passive"))
      (node (ref "U3") (pin "8") (pinfunction "8:VDD__8") (pintype "bidirectional"))
      (node (ref "U7") (pin "22") (pinfunction "VDD_22") (pintype "bidirectional"))
      (node (ref "U7") (pin "25") (pinfunction "VBAT_25") (pintype "bidirectional"))
    )
    (net (code "64") (name "5V") (class "Default")
      (node (ref "C1") (pin "2") (pinfunction "2_2") (pintype "passive"))
      (node (ref "C10") (pin "2") (pinfunction "2_2") (pintype "passive"))
      (node (ref "C14") (pin "2") (pinfunction "2_2") (pintype "passive"))
      (node (ref "D3") (pin "A") (pinfunction "ANODE_A") (pintype "passive"))
      (node (ref "EXT1") (pin "2") (pinfunction "2:5V_2") (pintype "bidirectional"))
      (node (ref "EXT2") (pin "2") (pinfunction "2:5V_2") (pintype "bidirectional"))
      (node (ref "GP12") (pin "VCC") (pinfunction "VCC_VCC") (pintype "bidirectional"))
      (node (ref "GP13") (pin "5V") (pinfunction "2:5V_5V") (pintype "bidirectional"))
      (node (ref "GPIO40") (pin "2") (pinfunction "5V_2") (pintype "bidirectional"))
      (node (ref "I2C") (pin "5V") (pinfunction "VCC_5V") (pintype "bidirectional"))
      (node (ref "LED1") (pin "VCC") (pinfunction "VCC_VCC") (pintype "bidirectional"))
      (node (ref "R28") (pin "2") (pinfunction "2_2") (pintype "bidirectional"))
      (node (ref "SPI-LED") (pin "5V") (pinfunction "VCC_5V") (pintype "bidirectional"))
      (node (ref "U$10") (pin "5") (pinfunction "5:VCC_5") (pintype "power_in"))
      (node (ref "U$9") (pin "5") (pinfunction "5:VCC_5") (pintype "power_in"))
    )
    (net (code "65") (name "5VL_JETSON") (class "Default")
      (node (ref "D3") (pin "K") (pinfunction "CATHODE_K") (pintype "passive"))
      (node (ref "U2") (pin "P$14") (pinfunction "5V_P$14") (pintype "bidirectional"))
      (node (ref "U2") (pin "P$28") (pinfunction "5V_P$28") (pintype "bidirectional"))
    )
    (net (code "66") (name "GND") (class "Default")
      (node (ref "C1") (pin "1") (pinfunction "1_1") (pintype "passive"))
      (node (ref "C10") (pin "1") (pinfunction "1_1") (pintype "passive"))
      (node (ref "C11") (pin "1") (pinfunction "1_1") (pintype "passive"))
      (node (ref "C12") (pin "1") (pinfunction "1_1") (pintype "passive"))
      (node (ref "C13") (pin "1") (pinfunction "1_1") (pintype "passive"))
      (node (ref "C14") (pin "1") (pinfunction "1_1") (pintype "passive"))
      (node (ref "C15") (pin "1") (pinfunction "1_1") (pintype "passive"))
      (node (ref "C16") (pin "1") (pinfunction "1_1") (pintype "passive"))
      (node (ref "C17") (pin "1") (pinfunction "1_1") (pintype "passive"))
      (node (ref "C18") (pin "1") (pinfunction "1_1") (pintype "passive"))
      (node (ref "C2") (pin "1") (pinfunction "1_1") (pintype "passive"))
      (node (ref "C20") (pin "1") (pinfunction "1_1") (pintype "passive"))
      (node (ref "C21") (pin "2") (pinfunction "2_2") (pintype "passive"))
      (node (ref "C23") (pin "2") (pinfunction "2_2") (pintype "passive"))
      (node (ref "C24") (pin "1") (pinfunction "1_1") (pintype "passive"))
      (node (ref "C25") (pin "1") (pinfunction "1_1") (pintype "passive"))
      (node (ref "C3") (pin "1") (pinfunction "1_1") (pintype "passive"))
      (node (ref "C4") (pin "1") (pinfunction "1_1") (pintype "passive"))
      (node (ref "C5") (pin "1") (pinfunction "1_1") (pintype "passive"))
      (node (ref "C6") (pin "1") (pinfunction "1_1") (pintype "passive"))
      (node (ref "C7") (pin "1") (pinfunction "1_1") (pintype "passive"))
      (node (ref "C8") (pin "1") (pinfunction "1_1") (pintype "passive"))
      (node (ref "C9") (pin "1") (pinfunction "1_1") (pintype "passive"))
      (node (ref "ESC_CON") (pin "1") (pinfunction "1:GND_1") (pintype "bidirectional"))
      (node (ref "EXT1") (pin "1") (pinfunction "1:GND_1") (pintype "bidirectional"))
      (node (ref "EXT2") (pin "1") (pinfunction "1:GND_1") (pintype "bidirectional"))
      (node (ref "GP12") (pin "GND") (pinfunction "GND_GND") (pintype "bidirectional"))
      (node (ref "GP13") (pin "GND") (pinfunction "1:GND_GND") (pintype "bidirectional"))
      (node (ref "GPIO40") (pin "14") (pinfunction "GND_14") (pintype "bidirectional"))
      (node (ref "GPIO40") (pin "20") (pinfunction "GND_20") (pintype "bidirectional"))
      (node (ref "GPIO40") (pin "25") (pinfunction "GND_25") (pintype "bidirectional"))
      (node (ref "GPIO40") (pin "30") (pinfunction "GND_30") (pintype "bidirectional"))
      (node (ref "GPIO40") (pin "34") (pinfunction "GND_34") (pintype "bidirectional"))
      (node (ref "GPIO40") (pin "39") (pinfunction "GND_39") (pintype "bidirectional"))
      (node (ref "GPIO40") (pin "9") (pinfunction "GND_9") (pintype "bidirectional"))
      (node (ref "I2C") (pin "GND") (pinfunction "GND_GND") (pintype "bidirectional"))
      (node (ref "IC1") (pin "2") (pinfunction "GND_2") (pintype "power_in"))
      (node (ref "IC2") (pin "1") (pinfunction "A0_1") (pintype "bidirectional"))
      (node (ref "IC2") (pin "14") (pinfunction "VSS_14") (pintype "bidirectional"))
      (node (ref "IC2") (pin "2") (pinfunction "A1_2") (pintype "bidirectional"))
      (node (ref "IC2") (pin "24") (pinfunction "A5_24") (pintype "bidirectional"))
      (node (ref "IC2") (pin "3") (pinfunction "A2_3") (pintype "bidirectional"))
      (node (ref "IC2") (pin "4") (pinfunction "A3_4") (pintype "bidirectional"))
      (node (ref "IC2") (pin "5") (pinfunction "A4_5") (pintype "bidirectional"))
      (node (ref "LED1") (pin "GND") (pinfunction "GND_GND") (pintype "bidirectional"))
      (node (ref "MOTOR") (pin "1") (pinfunction "1:GND_1") (pintype "bidirectional"))
      (node (ref "Q3") (pin "S") (pinfunction "S_S") (pintype "passive"))
      (node (ref "Q4") (pin "S") (pinfunction "S_S") (pintype "passive"))
      (node (ref "Q5") (pin "S") (pinfunction "S_S") (pintype "passive"))
      (node (ref "R1") (pin "1") (pinfunction "1_1") (pintype "bidirectional"))
      (node (ref "R13") (pin "2") (pinfunction "2_2") (pintype "bidirectional"))
      (node (ref "R17") (pin "1") (pinfunction "1_1") (pintype "bidirectional"))
      (node (ref "R24") (pin "2") (pinfunction "2_2") (pintype "bidirectional"))
      (node (ref "R28") (pin "1") (pinfunction "1_1") (pintype "bidirectional"))
      (node (ref "R3") (pin "1") (pinfunction "1_1") (pintype "bidirectional"))
      (node (ref "R32") (pin "2") (pinfunction "2_2") (pintype "bidirectional"))
      (node (ref "R33") (pin "2") (pinfunction "2_2") (pintype "bidirectional"))
      (node (ref "R36") (pin "1") (pinfunction "1_1") (pintype "bidirectional"))
      (node (ref "R40") (pin "2") (pinfunction "2_2") (pintype "bidirectional"))
      (node (ref "R41") (pin "2") (pinfunction "2_2") (pintype "bidirectional"))
      (node (ref "R42") (pin "2") (pinfunction "2_2") (pintype "bidirectional"))
      (node (ref "R45") (pin "1") (pinfunction "1_1") (pintype "bidirectional"))
      (node (ref "R46") (pin "1") (pinfunction "1_1") (pintype "bidirectional"))
      (node (ref "R5") (pin "1") (pinfunction "1_1") (pintype "bidirectional"))
      (node (ref "R53") (pin "1") (pinfunction "1_1") (pintype "bidirectional"))
      (node (ref "R54") (pin "1") (pinfunction "1_1") (pintype "bidirectional"))
      (node (ref "R55") (pin "1") (pinfunction "1_1") (pintype "bidirectional"))
      (node (ref "R6") (pin "2") (pinfunction "2_2") (pintype "bidirectional"))
      (node (ref "R7") (pin "1") (pinfunction "1_1") (pintype "bidirectional"))
      (node (ref "R9") (pin "1") (pinfunction "1_1") (pintype "bidirectional"))
      (node (ref "SPI-LED") (pin "GND") (pinfunction "GND_GND") (pintype "bidirectional"))
      (node (ref "U$1") (pin "13:ST_GND") (pinfunction "13:GND_13:ST_GND") (pintype "bidirectional"))
      (node (ref "U$1") (pin "17:TH_GND") (pinfunction "17:GND_17:TH_GND") (pintype "bidirectional"))
      (node (ref "U$1") (pin "3:GND3") (pinfunction "3:GND_3:GND3") (pintype "bidirectional"))
      (node (ref "U$1") (pin "6:GND2") (pinfunction "6:GND_6:GND2") (pintype "bidirectional"))
      (node (ref "U$1") (pin "9:GND1") (pinfunction "9:GND_9:GND1") (pintype "bidirectional"))
      (node (ref "U$10") (pin "1") (pinfunction "1:OE_1") (pintype "input"))
      (node (ref "U$10") (pin "3") (pinfunction "3:GND_3") (pintype "power_in"))
      (node (ref "U$11") (pin "#2") (pinfunction "2:CASE_GND_#2") (pintype "bidirectional"))
      (node (ref "U$13") (pin "18") (pinfunction "18:COM2_18") (pintype "bidirectional"))
      (node (ref "U$13") (pin "2") (pinfunction "2:GND_2") (pintype "power_in"))
      (node (ref "U$13") (pin "25") (pinfunction "25:GNDIO_25") (pintype "power_in"))
      (node (ref "U$3") (pin "15") (pinfunction "15:E_15") (pintype "bidirectional"))
      (node (ref "U$3") (pin "8") (pinfunction "8:GND_8") (pintype "bidirectional"))
      (node (ref "U$9") (pin "1") (pinfunction "1:OE_1") (pintype "input"))
      (node (ref "U$9") (pin "3") (pinfunction "3:GND_3") (pintype "power_in"))
      (node (ref "U2") (pin "P$13") (pinfunction "GND_P$13") (pintype "bidirectional"))
      (node (ref "U2") (pin "P$27") (pinfunction "GND_P$27") (pintype "bidirectional"))
      (node (ref "U3") (pin "5") (pinfunction "5:GND_5") (pintype "bidirectional"))
      (node (ref "U7") (pin "10") (pinfunction "D3_10") (pintype "bidirectional"))
      (node (ref "U7") (pin "14") (pinfunction "E/RD#_14") (pintype "bidirectional"))
      (node (ref "U7") (pin "15") (pinfunction "R/W#_15") (pintype "bidirectional"))
      (node (ref "U7") (pin "18") (pinfunction "CS#_18") (pintype "bidirectional"))
      (node (ref "U7") (pin "19") (pinfunction "BS2_19") (pintype "bidirectional"))
      (node (ref "U7") (pin "2") (pinfunction "VLSS_2") (pintype "bidirectional"))
      (node (ref "U7") (pin "21") (pinfunction "BS0_21") (pintype "bidirectional"))
      (node (ref "U7") (pin "23") (pinfunction "VSS_23") (pintype "bidirectional"))
      (node (ref "U7") (pin "6") (pinfunction "D7_6") (pintype "bidirectional"))
      (node (ref "U7") (pin "7") (pinfunction "D6_7") (pintype "bidirectional"))
      (node (ref "U7") (pin "8") (pinfunction "D5_8") (pintype "bidirectional"))
      (node (ref "U7") (pin "9") (pinfunction "D4_9") (pintype "bidirectional"))
    )
    (net (code "67") (name "NC5") (class "Default")
      (node (ref "U2") (pin "P$10") (pinfunction "PA5_A9_D9_MISO_P$10") (pintype "bidirectional"))
      (node (ref "U2") (pin "P$24") (pinfunction "PA5_A9_D9_MISO_P$24") (pintype "bidirectional"))
    )
    (net (code "68") (name "Net-(C12-Pad2)") (class "Default")
      (node (ref "C12") (pin "2") (pinfunction "2_2") (pintype "passive"))
      (node (ref "D1") (pin "ANODE") (pinfunction "ANODE_ANODE") (pintype "bidirectional"))
      (node (ref "R25") (pin "2") (pinfunction "2_2") (pintype "bidirectional"))
      (node (ref "R31") (pin "1") (pinfunction "1_1") (pintype "bidirectional"))
    )
    (net (code "69") (name "Net-(EXT1-4:LRCK)") (class "Default")
      (node (ref "EXT1") (pin "4") (pinfunction "4:LRCK_4") (pintype "bidirectional"))
      (node (ref "R38") (pin "2") (pinfunction "2_2") (pintype "bidirectional"))
    )
    (net (code "70") (name "Net-(EXT1-5:BCLK)") (class "Default")
      (node (ref "EXT1") (pin "5") (pinfunction "5:BCLK_5") (pintype "bidirectional"))
      (node (ref "R30") (pin "2") (pinfunction "2_2") (pintype "bidirectional"))
    )
    (net (code "71") (name "Net-(EXT1-7:DOUT)") (class "Default")
      (node (ref "EXT1") (pin "7") (pinfunction "7:DOUT_7") (pintype "bidirectional"))
      (node (ref "R18") (pin "2") (pinfunction "2_2") (pintype "bidirectional"))
      (node (ref "R41") (pin "1") (pinfunction "1_1") (pintype "bidirectional"))
    )
    (net (code "72") (name "Net-(IC1-BYPASS)") (class "Default")
      (node (ref "C6") (pin "2") (pinfunction "2_2") (pintype "passive"))
      (node (ref "IC1") (pin "4") (pinfunction "BYPASS_4") (pintype "bidirectional"))
    )
    (net (code "73") (name "Net-(IC2-EXTCLK)") (class "Default")
      (node (ref "C3") (pin "2") (pinfunction "2_2") (pintype "passive"))
      (node (ref "IC2") (pin "25") (pinfunction "EXTCLK_25") (pintype "bidirectional"))
      (node (ref "R1") (pin "2") (pinfunction "2_2") (pintype "bidirectional"))
      (node (ref "U$11") (pin "#3") (pinfunction "3:OUTPUT_#3") (pintype "bidirectional"))
    )
    (net (code "74") (name "Net-(IC2-LED14)") (class "Default")
      (node (ref "IC2") (pin "21") (pinfunction "LED14_21") (pintype "bidirectional"))
      (node (ref "TP2") (pin "TP") (pinfunction "TP_TP") (pintype "passive"))
    )
    (net (code "75") (name "Net-(IC2-OE)") (class "Default")
      (node (ref "IC2") (pin "23") (pinfunction "OE_23") (pintype "bidirectional"))
      (node (ref "R3") (pin "2") (pinfunction "2_2") (pintype "bidirectional"))
    )
    (net (code "76") (name "Net-(Q3-PadD)") (class "Default")
      (node (ref "Q3") (pin "D") (pinfunction "D_D") (pintype "passive"))
      (node (ref "R26") (pin "2") (pinfunction "2_2") (pintype "bidirectional"))
    )
    (net (code "77") (name "Net-(Q3-PadG)") (class "Default")
      (node (ref "Q3") (pin "G") (pinfunction "G_G") (pintype "passive"))
      (node (ref "R24") (pin "1") (pinfunction "1_1") (pintype "bidirectional"))
      (node (ref "R8") (pin "1") (pinfunction "1_1") (pintype "bidirectional"))
    )
    (net (code "78") (name "Net-(Q4-PadD)") (class "Default")
      (node (ref "Q4") (pin "D") (pinfunction "D_D") (pintype "passive"))
      (node (ref "R27") (pin "2") (pinfunction "2_2") (pintype "bidirectional"))
    )
    (net (code "79") (name "Net-(Q4-PadG)") (class "Default")
      (node (ref "Q4") (pin "G") (pinfunction "G_G") (pintype "passive"))
      (node (ref "R33") (pin "1") (pinfunction "1_1") (pintype "bidirectional"))
      (node (ref "R35") (pin "2") (pinfunction "2_2") (pintype "bidirectional"))
    )
    (net (code "80") (name "Net-(Q5-PadD)") (class "Default")
      (node (ref "Q5") (pin "D") (pinfunction "D_D") (pintype "passive"))
      (node (ref "R29") (pin "2") (pinfunction "2_2") (pintype "bidirectional"))
    )
    (net (code "81") (name "Net-(Q5-PadG)") (class "Default")
      (node (ref "Q5") (pin "G") (pinfunction "G_G") (pintype "passive"))
      (node (ref "R32") (pin "1") (pinfunction "1_1") (pintype "bidirectional"))
      (node (ref "R34") (pin "2") (pinfunction "2_2") (pintype "bidirectional"))
    )
    (net (code "82") (name "Net-(R7-Pad2)") (class "Default")
      (node (ref "R7") (pin "2") (pinfunction "2_2") (pintype "bidirectional"))
      (node (ref "RCPWR") (pin "CATHODE") (pinfunction "CATHODE_CATHODE") (pintype "passive"))
    )
    (net (code "83") (name "Net-(U$3-10:B2)") (class "Default")
      (node (ref "R46") (pin "2") (pinfunction "2_2") (pintype "bidirectional"))
      (node (ref "U$3") (pin "10") (pinfunction "10:B2_10") (pintype "bidirectional"))
    )
    (net (code "84") (name "Net-(U$3-11:A2)") (class "Default")
      (node (ref "R45") (pin "2") (pinfunction "2_2") (pintype "bidirectional"))
      (node (ref "U$3") (pin "11") (pinfunction "11:A2_11") (pintype "bidirectional"))
    )
    (net (code "85") (name "Net-(U$3-13:B3)") (class "Default")
      (node (ref "R17") (pin "2") (pinfunction "2_2") (pintype "bidirectional"))
      (node (ref "U$3") (pin "13") (pinfunction "13:B3_13") (pintype "bidirectional"))
    )
    (net (code "86") (name "Net-(U$3-14:A3)") (class "Default")
      (node (ref "R9") (pin "2") (pinfunction "2_2") (pintype "bidirectional"))
      (node (ref "U$3") (pin "14") (pinfunction "14:A3_14") (pintype "bidirectional"))
    )
    (net (code "87") (name "Net-(U$9-4:Y)") (class "Default")
      (node (ref "LED1") (pin "SDI") (pinfunction "SDI_SDI") (pintype "bidirectional"))
      (node (ref "U$9") (pin "4") (pinfunction "4:Y_4") (pintype "output"))
    )
    (net (code "88") (name "Net-(U$10-4:Y)") (class "Default")
      (node (ref "LED1") (pin "CKI") (pinfunction "CKI_CKI") (pintype "bidirectional"))
      (node (ref "U$10") (pin "4") (pinfunction "4:Y_4") (pintype "output"))
    )
    (net (code "89") (name "Net-(U$13-4:NBOOT)") (class "Default")
      (node (ref "R60") (pin "1") (pinfunction "1_1") (pintype "bidirectional"))
      (node (ref "U$13") (pin "4") (pinfunction "4:NBOOT_4") (pintype "input"))
    )
    (net (code "90") (name "Net-(U$13-5:PS1)") (class "Default")
      (node (ref "R53") (pin "2") (pinfunction "2_2") (pintype "bidirectional"))
      (node (ref "U$13") (pin "5") (pinfunction "5:PS1_5") (pintype "input"))
    )
    (net (code "91") (name "Net-(U$13-6:PS0)") (class "Default")
      (node (ref "R54") (pin "2") (pinfunction "2_2") (pintype "bidirectional"))
      (node (ref "U$13") (pin "6") (pinfunction "6:PS0_6") (pintype "input"))
    )
    (net (code "92") (name "Net-(U$13-7:SWDIO)") (class "Default")
      (node (ref "TP4") (pin "TP") (pinfunction "TP_TP") (pintype "passive"))
      (node (ref "U$13") (pin "7") (pinfunction "7:SWDIO_7") (pintype "bidirectional"))
    )
    (net (code "93") (name "Net-(U$13-8:SWCLK)") (class "Default")
      (node (ref "TP5") (pin "TP") (pinfunction "TP_TP") (pintype "passive"))
      (node (ref "U$13") (pin "8") (pinfunction "8:SWCLK_8") (pintype "input"))
    )
    (net (code "94") (name "Net-(U$13-9:CAP)") (class "Default")
      (node (ref "C20") (pin "2") (pinfunction "2_2") (pintype "passive"))
      (node (ref "U$13") (pin "9") (pinfunction "9:CAP_9") (pintype "bidirectional"))
    )
    (net (code "95") (name "Net-(U$13-10:BL_IND)") (class "Default")
      (node (ref "TP3") (pin "TP") (pinfunction "TP_TP") (pintype "passive"))
      (node (ref "U$13") (pin "10") (pinfunction "10:BL_IND_10") (pintype "output"))
    )
    (net (code "96") (name "Net-(U$13-11:NRESET)") (class "Default")
      (node (ref "R56") (pin "1") (pinfunction "1_1") (pintype "bidirectional"))
      (node (ref "R61") (pin "2") (pinfunction "2_2") (pintype "bidirectional"))
      (node (ref "U$13") (pin "11") (pinfunction "11:NRESET_11") (pintype "bidirectional"))
    )
    (net (code "97") (name "Net-(U$13-17:COM3)") (class "Default")
      (node (ref "R55") (pin "2") (pinfunction "2_2") (pintype "bidirectional"))
      (node (ref "R62") (pin "1") (pinfunction "1_1") (pintype "bidirectional"))
      (node (ref "U$13") (pin "17") (pinfunction "17:COM3_17") (pintype "input"))
    )
    (net (code "98") (name "Net-(U$13-26:XOUT32)") (class "Default")
      (node (ref "C23") (pin "1") (pinfunction "1_1") (pintype "passive"))
      (node (ref "U$13") (pin "26") (pinfunction "26:XOUT32_26") (pintype "output"))
      (node (ref "X1") (pin "2") (pinfunction "P$2_2") (pintype "bidirectional"))
    )
    (net (code "99") (name "Net-(U$13-27:XIN32)") (class "Default")
      (node (ref "C21") (pin "1") (pinfunction "1_1") (pintype "passive"))
      (node (ref "U$13") (pin "27") (pinfunction "27:XIN32_27") (pintype "input"))
      (node (ref "X1") (pin "1") (pinfunction "P$1_1") (pintype "bidirectional"))
    )
    (net (code "100") (name "Net-(U1-C)") (class "Default")
      (node (ref "R26") (pin "1") (pinfunction "1_1") (pintype "bidirectional"))
      (node (ref "U1") (pin "2") (pinfunction "C_2") (pintype "passive"))
    )
    (net (code "101") (name "Net-(U3-1:AN1)") (class "Default")
      (node (ref "R16") (pin "1") (pinfunction "1_1") (pintype "bidirectional"))
      (node (ref "U3") (pin "1") (pinfunction "1:AN1_1") (pintype "bidirectional"))
    )
    (net (code "102") (name "Net-(U3-2:CA1)") (class "Default")
      (node (ref "R29") (pin "1") (pinfunction "1_1") (pintype "bidirectional"))
      (node (ref "U3") (pin "2") (pinfunction "2:CA1_2") (pintype "bidirectional"))
    )
    (net (code "103") (name "Net-(U3-3:CA2)") (class "Default")
      (node (ref "R27") (pin "1") (pinfunction "1_1") (pintype "bidirectional"))
      (node (ref "U3") (pin "3") (pinfunction "3:CA2_3") (pintype "bidirectional"))
    )
    (net (code "104") (name "Net-(U3-4:AN2)") (class "Default")
      (node (ref "R15") (pin "1") (pinfunction "1_1") (pintype "bidirectional"))
      (node (ref "U3") (pin "4") (pinfunction "4:AN2_4") (pintype "bidirectional"))
    )
    (net (code "105") (name "Net-(U3-6:OUT2)") (class "Default")
      (node (ref "U2") (pin "P$16") (pinfunction "PA4_A1_D1_P$16") (pintype "bidirectional"))
      (node (ref "U2") (pin "P$2") (pinfunction "PA4_A1_D1_P$2") (pintype "bidirectional"))
      (node (ref "U3") (pin "6") (pinfunction "6:OUT2_6") (pintype "bidirectional"))
    )
    (net (code "106") (name "Net-(U3-7:OUT1)") (class "Default")
      (node (ref "U2") (pin "P$1") (pinfunction "PA02_A0_D0_P$1") (pintype "bidirectional"))
      (node (ref "U2") (pin "P$15") (pinfunction "PA02_A0_D0_P$15") (pintype "bidirectional"))
      (node (ref "U3") (pin "7") (pinfunction "7:OUT1_7") (pintype "bidirectional"))
    )
    (net (code "107") (name "Net-(U7-BS1)") (class "Default")
      (node (ref "R19") (pin "2") (pinfunction "2_2") (pintype "bidirectional"))
      (node (ref "U7") (pin "20") (pinfunction "BS1_20") (pintype "bidirectional"))
    )
    (net (code "108") (name "Net-(U7-C1N)") (class "Default")
      (node (ref "C19") (pin "1") (pinfunction "1_1") (pintype "passive"))
      (node (ref "U7") (pin "26") (pinfunction "C1N_26") (pintype "bidirectional"))
    )
    (net (code "109") (name "Net-(U7-C1P)") (class "Default")
      (node (ref "C19") (pin "2") (pinfunction "2_2") (pintype "passive"))
      (node (ref "U7") (pin "27") (pinfunction "C1P_27") (pintype "bidirectional"))
    )
    (net (code "110") (name "Net-(U7-C2N)") (class "Default")
      (node (ref "C22") (pin "1") (pinfunction "1_1") (pintype "passive"))
      (node (ref "U7") (pin "28") (pinfunction "C2N_28") (pintype "bidirectional"))
    )
    (net (code "111") (name "Net-(U7-C2P)") (class "Default")
      (node (ref "C22") (pin "2") (pinfunction "2_2") (pintype "passive"))
      (node (ref "U7") (pin "29") (pinfunction "C2P_29") (pintype "bidirectional"))
    )
    (net (code "112") (name "Net-(U7-D{slash}C#)") (class "Default")
      (node (ref "R36") (pin "2") (pinfunction "2_2") (pintype "bidirectional"))
      (node (ref "R37") (pin "1") (pinfunction "1_1") (pintype "bidirectional"))
      (node (ref "U7") (pin "16") (pinfunction "D/C#_16") (pintype "bidirectional"))
    )
    (net (code "113") (name "Net-(U7-IREF)") (class "Default")
      (node (ref "R13") (pin "1") (pinfunction "1_1") (pintype "bidirectional"))
      (node (ref "U7") (pin "5") (pinfunction "IREF_5") (pintype "bidirectional"))
    )
    (net (code "114") (name "Net-(U7-RES#)") (class "Default")
      (node (ref "R31") (pin "2") (pinfunction "2_2") (pintype "bidirectional"))
      (node (ref "U7") (pin "17") (pinfunction "RES#_17") (pintype "bidirectional"))
    )
    (net (code "115") (name "Net-(U7-VCC)") (class "Default")
      (node (ref "C13") (pin "2") (pinfunction "2_2") (pintype "passive"))
      (node (ref "U7") (pin "3") (pinfunction "VCC_3") (pintype "bidirectional"))
    )
    (net (code "116") (name "Net-(U7-VCOMH)") (class "Default")
      (node (ref "C16") (pin "2") (pinfunction "2_2") (pintype "passive"))
      (node (ref "U7") (pin "4") (pinfunction "VCOMH_4") (pintype "bidirectional"))
    )
    (net (code "117") (name "SENSOR1") (class "Default")
      (node (ref "R47") (pin "2") (pinfunction "2_2") (pintype "bidirectional"))
      (node (ref "U2") (pin "P$21") (pinfunction "PB08_A6_D6_TX_P$21") (pintype "bidirectional"))
      (node (ref "U2") (pin "P$7") (pinfunction "PB08_A6_D6_TX_P$7") (pintype "bidirectional"))
    )
    (net (code "118") (name "SENSOR2") (class "Default")
      (node (ref "R48") (pin "2") (pinfunction "2_2") (pintype "bidirectional"))
      (node (ref "U2") (pin "P$22") (pinfunction "PB09_A7_D7_RX_P$22") (pintype "bidirectional"))
      (node (ref "U2") (pin "P$8") (pinfunction "PB09_A7_D7_RX_P$8") (pintype "bidirectional"))
    )
    (net (code "119") (name "SENSOR3") (class "Default")
      (node (ref "R49") (pin "2") (pinfunction "2_2") (pintype "bidirectional"))
      (node (ref "S3") (pin "1") (pinfunction "1_1") (pintype "passive"))
    )
    (net (code "120") (name "unconnected-(GPIO40-CE1-Pad26)") (class "Default")
      (node (ref "GPIO40") (pin "26") (pinfunction "CE1_26") (pintype "bidirectional"))
    )
    (net (code "121") (name "unconnected-(GPIO40-ID_SC-Pad28)") (class "Default")
      (node (ref "GPIO40") (pin "28") (pinfunction "ID_SC_28") (pintype "bidirectional"))
    )
    (net (code "122") (name "unconnected-(GPIO40-ID_SD-Pad27)") (class "Default")
      (node (ref "GPIO40") (pin "27") (pinfunction "ID_SD_27") (pintype "bidirectional"))
    )
    (net (code "123") (name "unconnected-(IC2-LED2-Pad8)") (class "Default")
      (node (ref "IC2") (pin "8") (pinfunction "LED2_8") (pintype "bidirectional"))
    )
    (net (code "124") (name "unconnected-(IC2-LED3-Pad9)") (class "Default")
      (node (ref "IC2") (pin "9") (pinfunction "LED3_9") (pintype "bidirectional"))
    )
    (net (code "125") (name "unconnected-(IC2-LED4-Pad10)") (class "Default")
      (node (ref "IC2") (pin "10") (pinfunction "LED4_10") (pintype "bidirectional"))
    )
    (net (code "126") (name "unconnected-(IC2-LED5-Pad11)") (class "Default")
      (node (ref "IC2") (pin "11") (pinfunction "LED5_11") (pintype "bidirectional"))
    )
    (net (code "127") (name "unconnected-(IC2-LED6-Pad12)") (class "Default")
      (node (ref "IC2") (pin "12") (pinfunction "LED6_12") (pintype "bidirectional"))
    )
    (net (code "128") (name "unconnected-(IC2-LED7-Pad13)") (class "Default")
      (node (ref "IC2") (pin "13") (pinfunction "LED7_13") (pintype "bidirectional"))
    )
    (net (code "129") (name "unconnected-(IC2-LED8-Pad15)") (class "Default")
      (node (ref "IC2") (pin "15") (pinfunction "LED8_15") (pintype "bidirectional"))
    )
    (net (code "130") (name "unconnected-(IC2-LED9-Pad16)") (class "Default")
      (node (ref "IC2") (pin "16") (pinfunction "LED9_16") (pintype "bidirectional"))
    )
    (net (code "131") (name "unconnected-(IC2-LED10-Pad17)") (class "Default")
      (node (ref "IC2") (pin "17") (pinfunction "LED10_17") (pintype "bidirectional"))
    )
    (net (code "132") (name "unconnected-(IC2-LED11-Pad18)") (class "Default")
      (node (ref "IC2") (pin "18") (pinfunction "LED11_18") (pintype "bidirectional"))
    )
    (net (code "133") (name "unconnected-(IC2-LED12-Pad19)") (class "Default")
      (node (ref "IC2") (pin "19") (pinfunction "LED12_19") (pintype "bidirectional"))
    )
    (net (code "134") (name "unconnected-(IC2-LED13-Pad20)") (class "Default")
      (node (ref "IC2") (pin "20") (pinfunction "LED13_20") (pintype "bidirectional"))
    )
    (net (code "135") (name "unconnected-(IC2-LED15-Pad22)") (class "Default")
      (node (ref "IC2") (pin "22") (pinfunction "LED15_22") (pintype "bidirectional"))
    )
    (net (code "136") (name "unconnected-(U$3-9:Y2-Pad9)") (class "Default")
      (node (ref "U$3") (pin "9") (pinfunction "9:Y2_9") (pintype "bidirectional"))
    )
    (net (code "137") (name "unconnected-(U$3-12:Y3-Pad12)") (class "Default")
      (node (ref "U$3") (pin "12") (pinfunction "12:Y3_12") (pintype "bidirectional"))
    )
    (net (code "138") (name "unconnected-(U$13-1:PIN1-Pad1)") (class "Default")
      (node (ref "U$13") (pin "1") (pinfunction "1:PIN1_1") (pintype "no_connect"))
    )
    (net (code "139") (name "unconnected-(U$13-12:PIN12-Pad12)") (class "Default")
      (node (ref "U$13") (pin "12") (pinfunction "12:PIN12_12") (pintype "no_connect"))
    )
    (net (code "140") (name "unconnected-(U$13-13:PIN13-Pad13)") (class "Default")
      (node (ref "U$13") (pin "13") (pinfunction "13:PIN13_13") (pintype "no_connect"))
    )
    (net (code "141") (name "unconnected-(U$13-14:INT-Pad14)") (class "Default")
      (node (ref "U$13") (pin "14") (pinfunction "14:INT_14") (pintype "output"))
    )
    (net (code "142") (name "unconnected-(U$13-15:PIN15-Pad15)") (class "Default")
      (node (ref "U$13") (pin "15") (pinfunction "15:PIN15_15") (pintype "no_connect"))
    )
    (net (code "143") (name "unconnected-(U$13-16:PIN16-Pad16)") (class "Default")
      (node (ref "U$13") (pin "16") (pinfunction "16:PIN16_16") (pintype "no_connect"))
    )
    (net (code "144") (name "unconnected-(U$13-21:PIN21-Pad21)") (class "Default")
      (node (ref "U$13") (pin "21") (pinfunction "21:PIN21_21") (pintype "no_connect"))
    )
    (net (code "145") (name "unconnected-(U$13-22:PIN22-Pad22)") (class "Default")
      (node (ref "U$13") (pin "22") (pinfunction "22:PIN22_22") (pintype "no_connect"))
    )
    (net (code "146") (name "unconnected-(U$13-23:PIN23-Pad23)") (class "Default")
      (node (ref "U$13") (pin "23") (pinfunction "23:PIN23_23") (pintype "no_connect"))
    )
    (net (code "147") (name "unconnected-(U$13-24:PIN24-Pad24)") (class "Default")
      (node (ref "U$13") (pin "24") (pinfunction "24:PIN24_24") (pintype "no_connect"))
    )
    (net (code "148") (name "unconnected-(U7-NC-Pad1)") (class "Default")
      (node (ref "U7") (pin "1") (pinfunction "NC_1") (pintype "bidirectional"))
    )
    (net (code "149") (name "unconnected-(U7-NC-Pad24)") (class "Default")
      (node (ref "U7") (pin "24") (pinfunction "NC_24") (pintype "bidirectional"))
    )
    (net (code "150") (name "unconnected-(U7-NC-Pad30)") (class "Default")
      (node (ref "U7") (pin "30") (pinfunction "NC_30") (pintype "bidirectional"))
    )
  )
)
